# SSRPGenericTelemetryModule.net
KiCad netlist of a schematic drawn in EAGLE
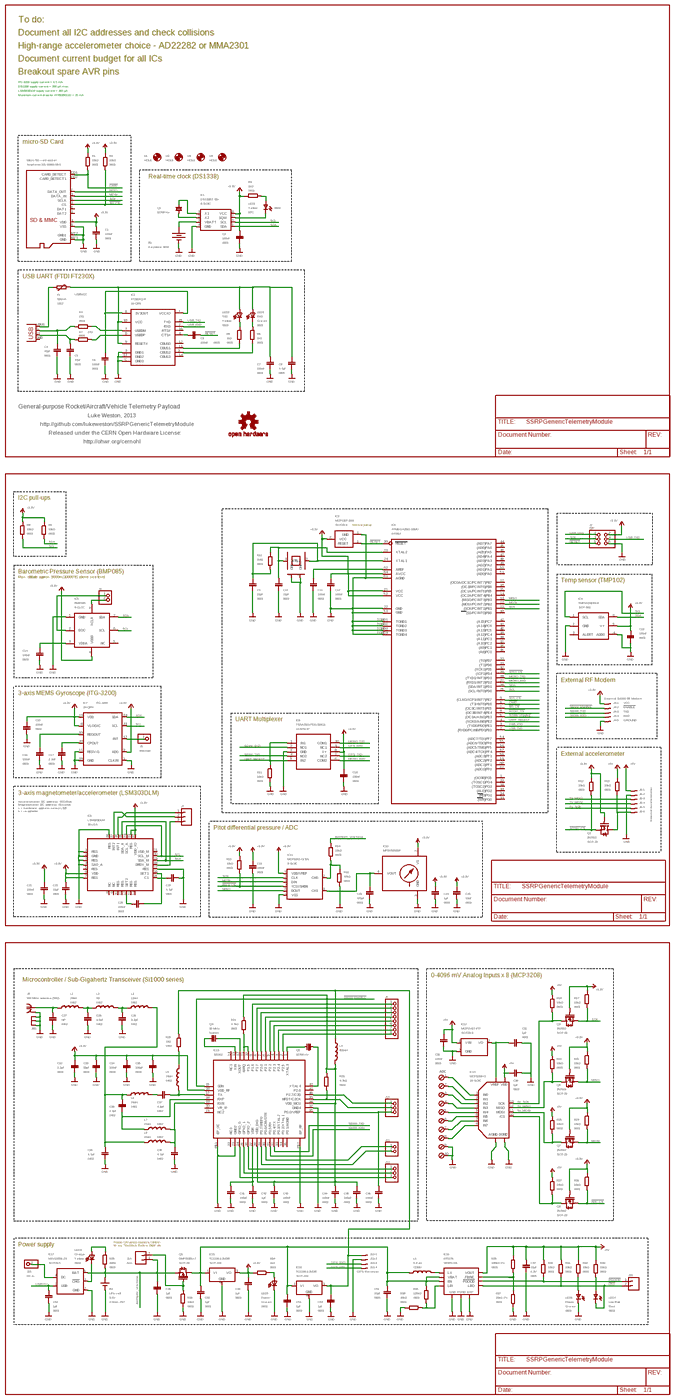
[diagram p0: schematic, sheet 1, overview]
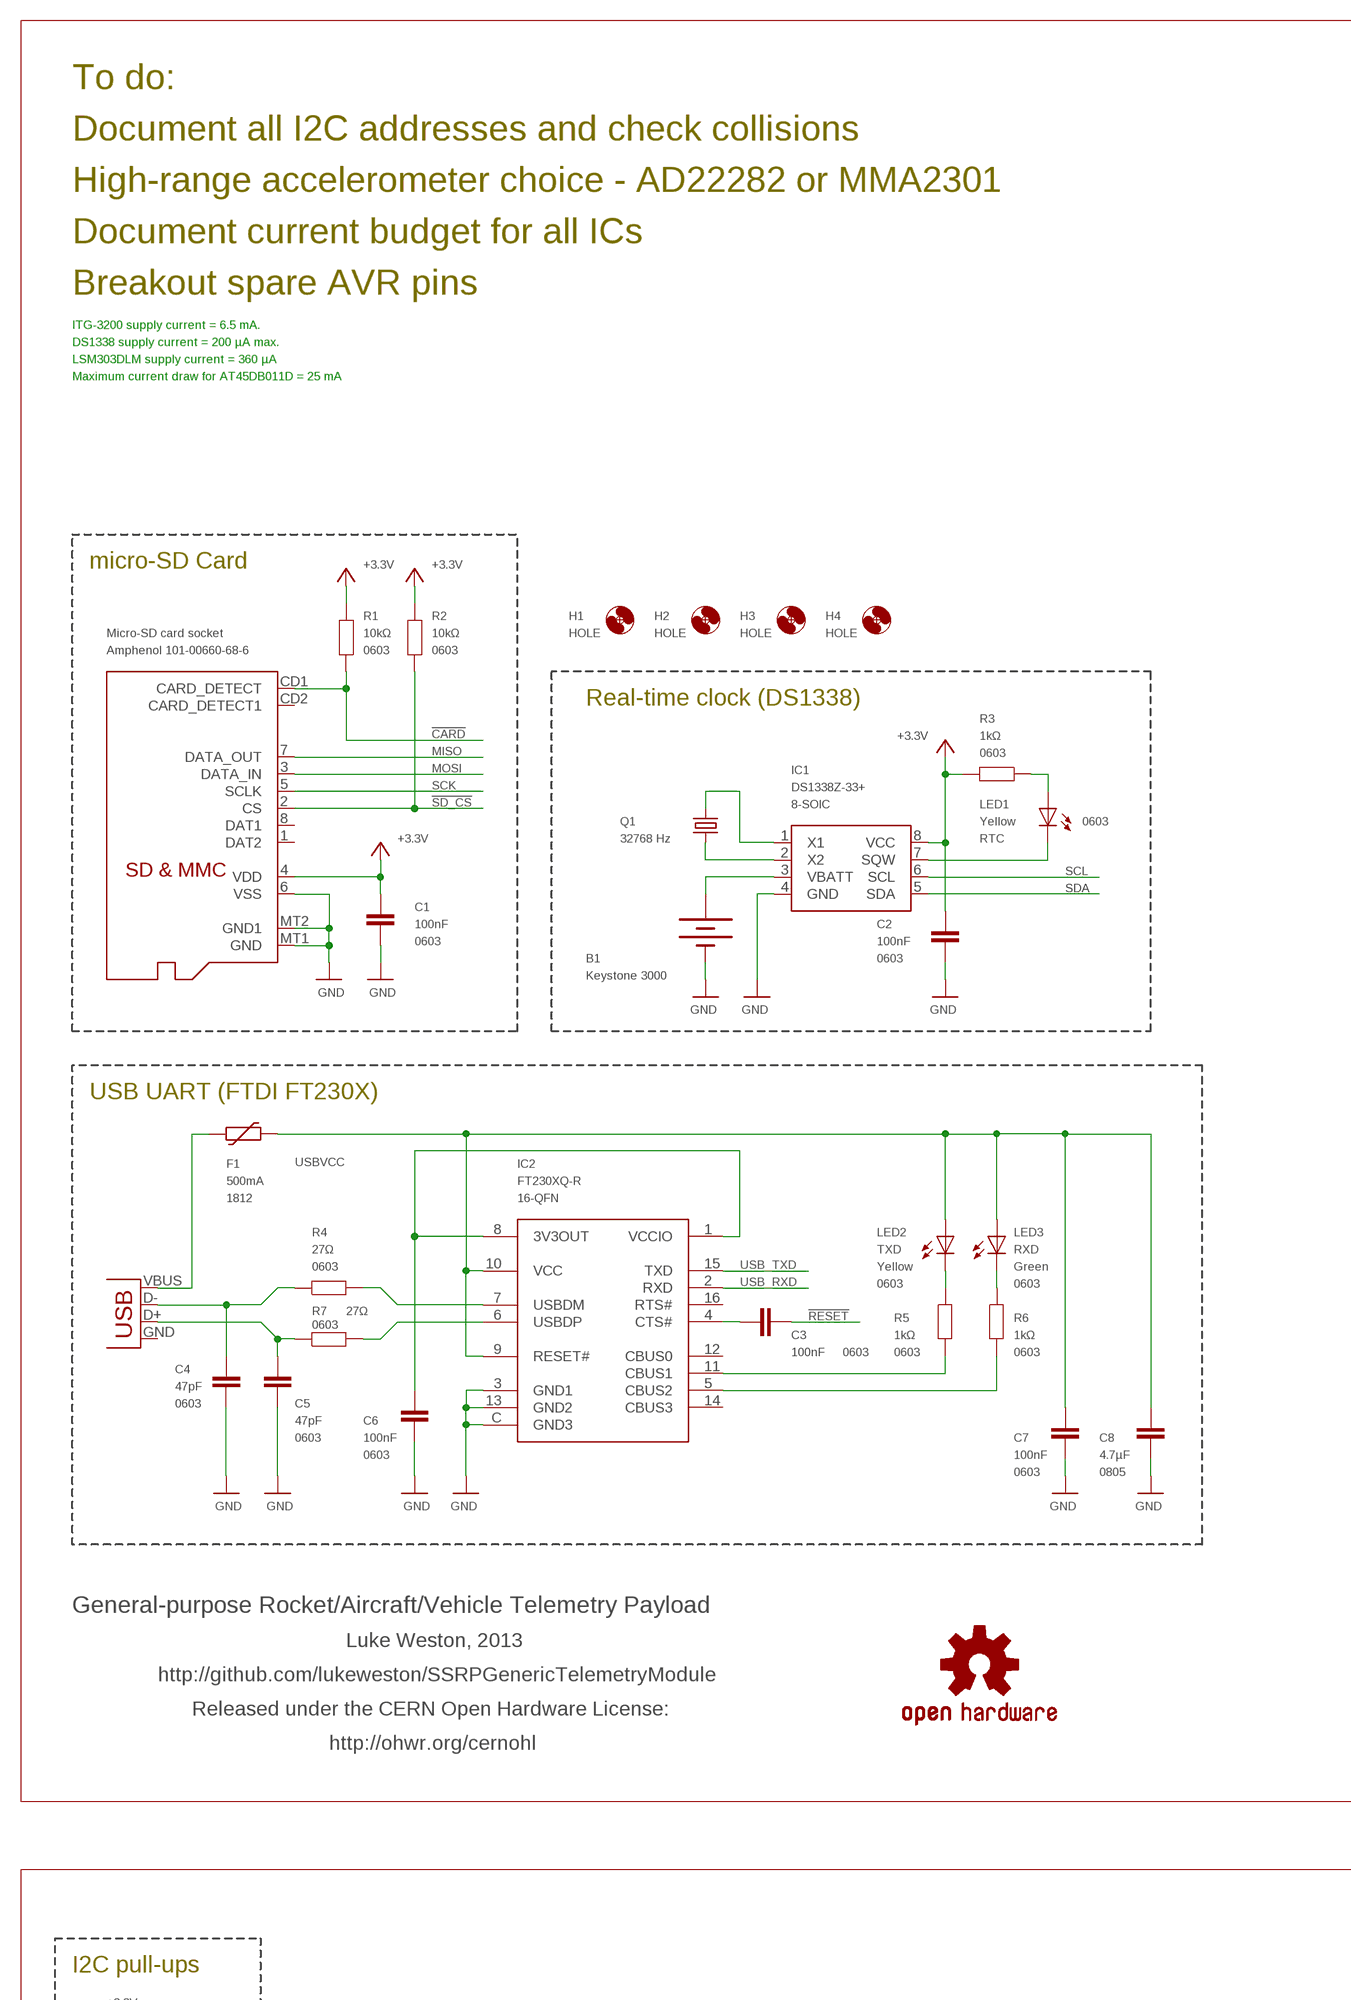
[diagram p1: schematic, sheet 1, part 1 of 6]
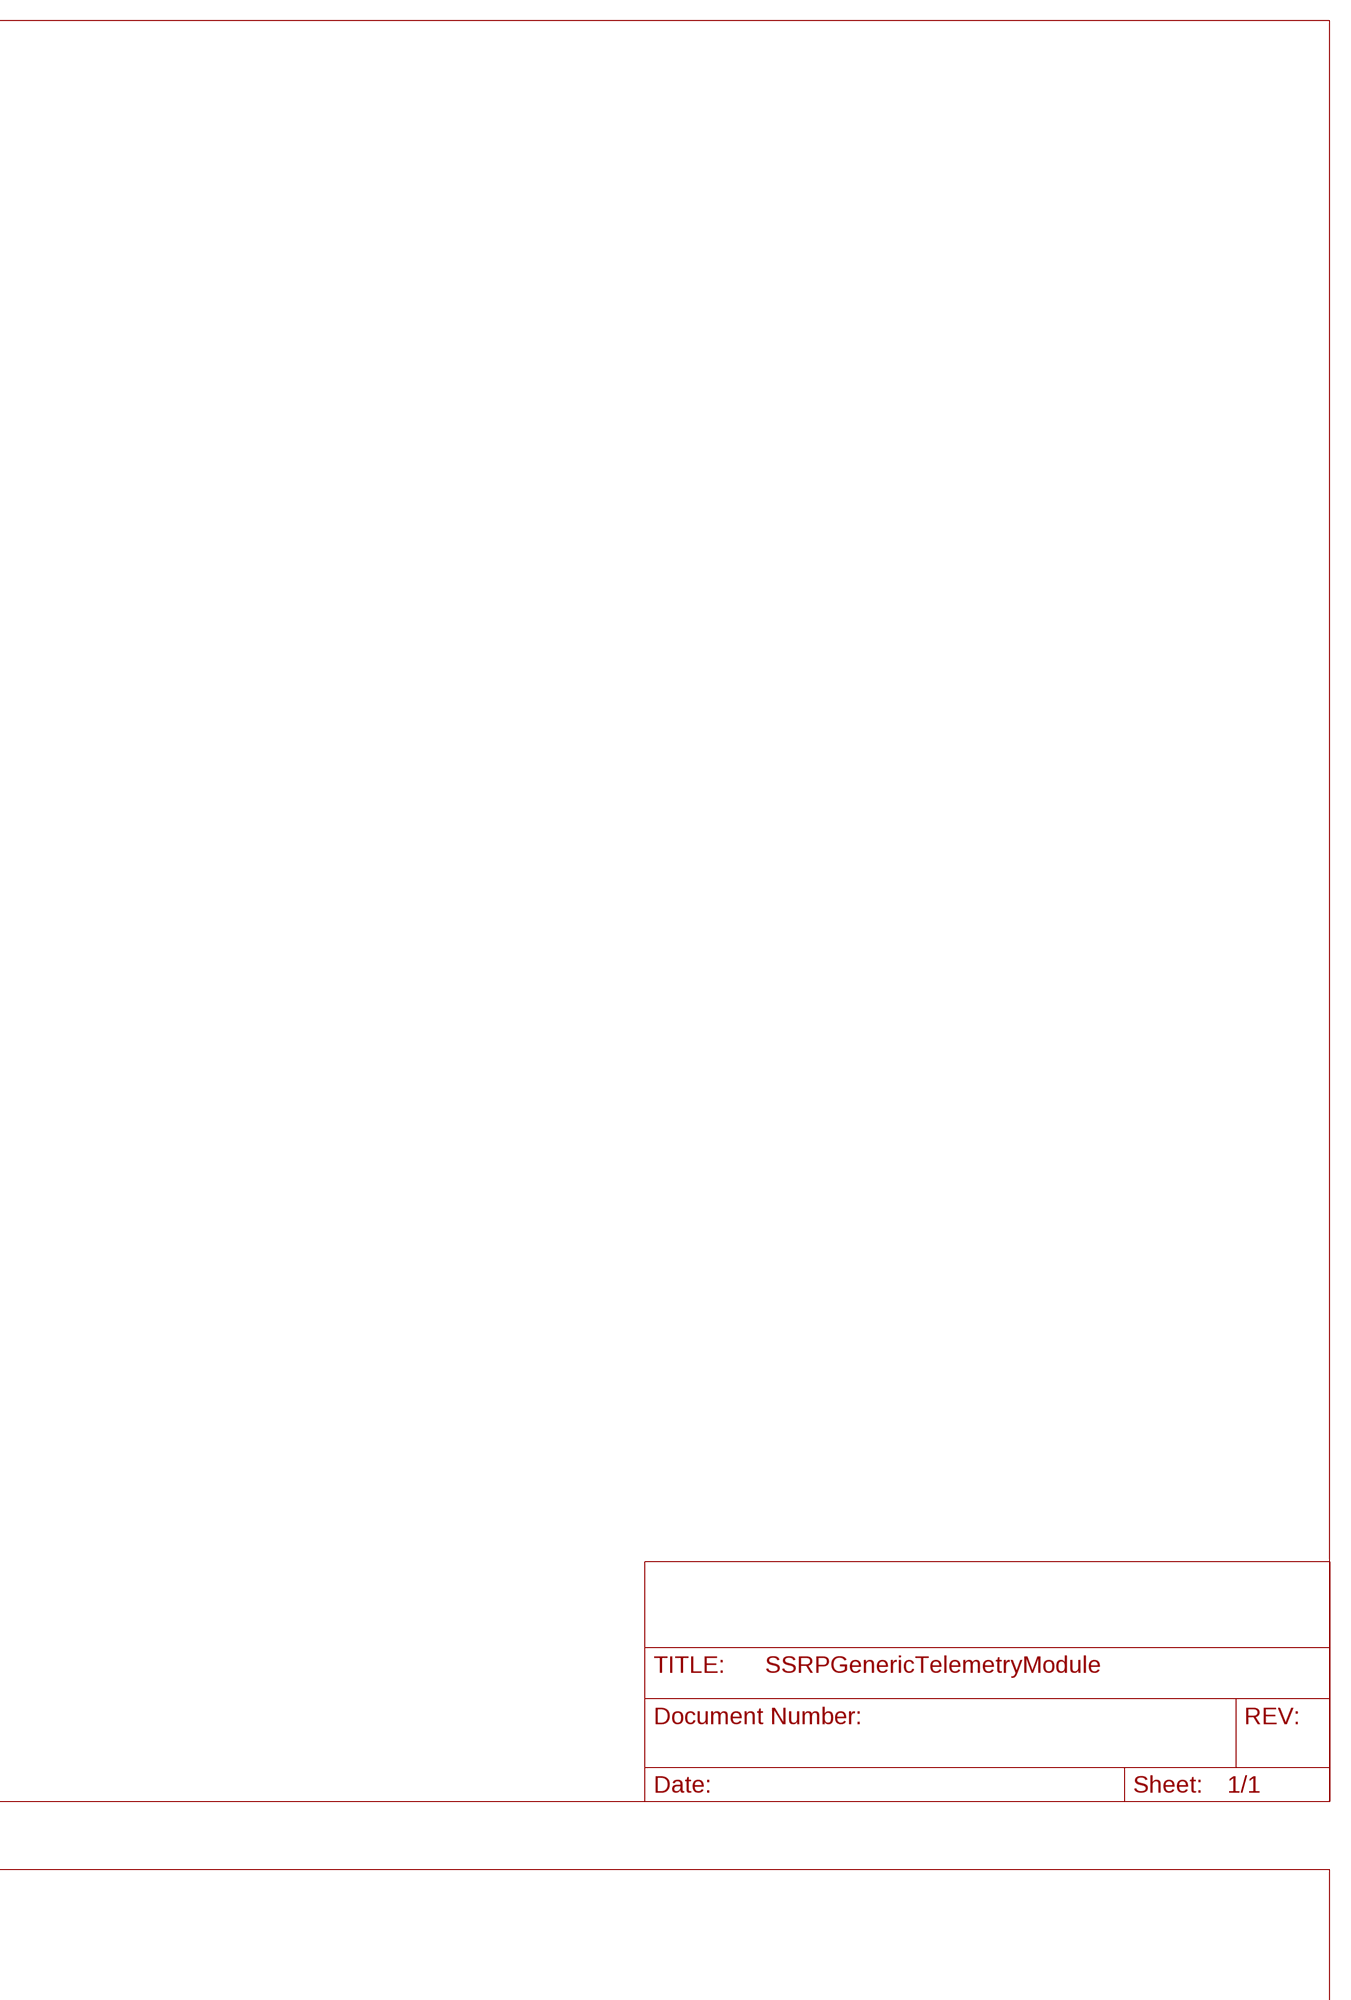
[diagram p2: schematic, sheet 1, part 2 of 6]
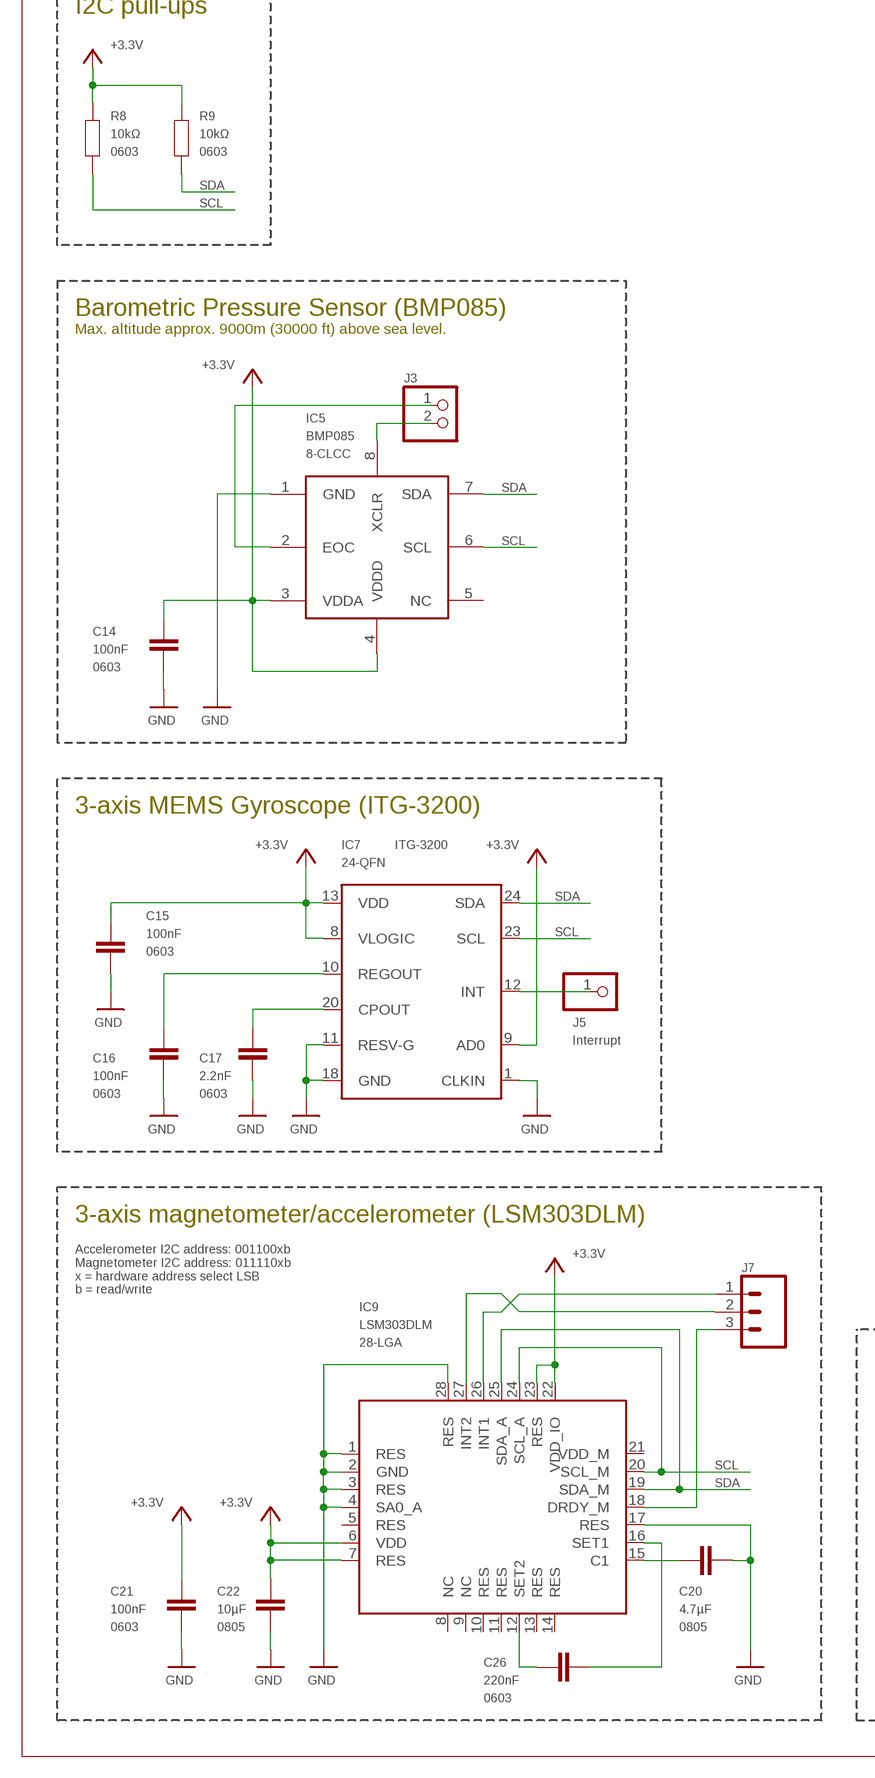
[diagram p3: schematic, sheet 1, part 3 of 6]
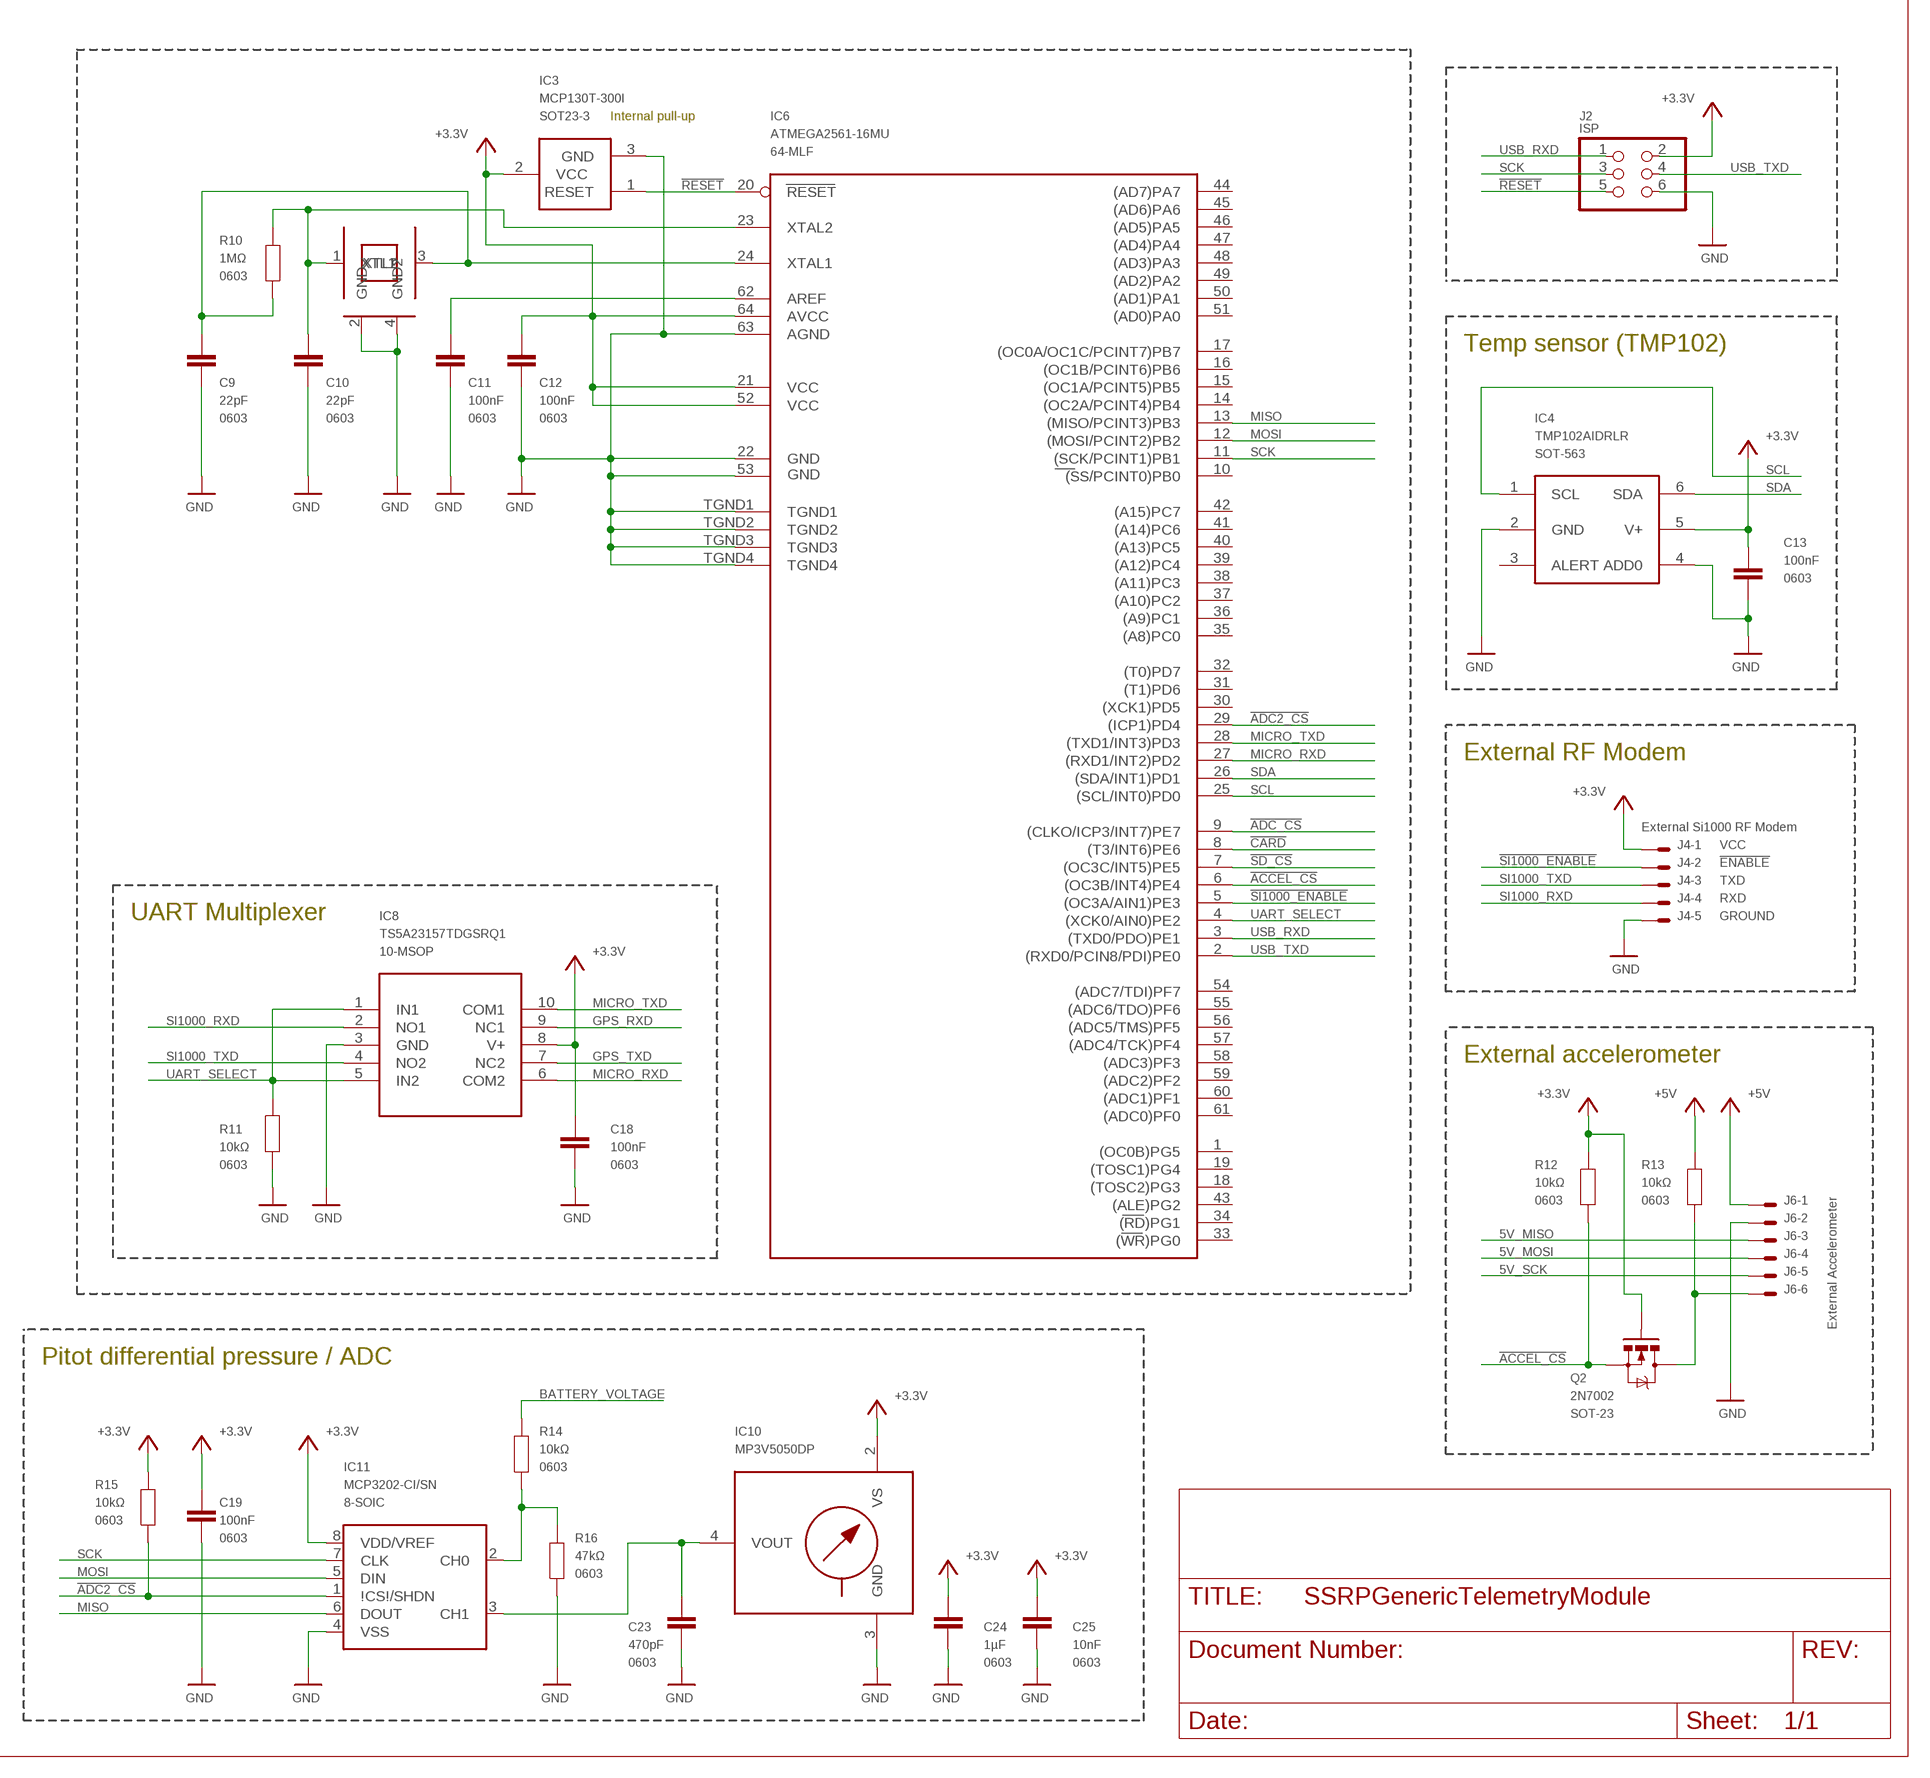
[diagram p4: schematic, sheet 1, part 4 of 6]
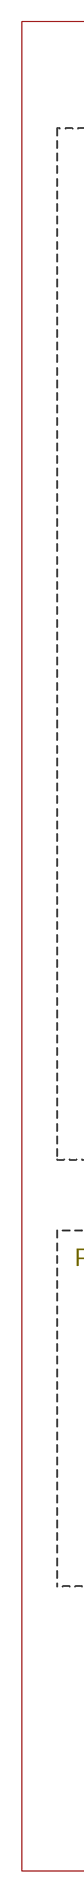
[diagram p5: schematic, sheet 1, part 5 of 6]
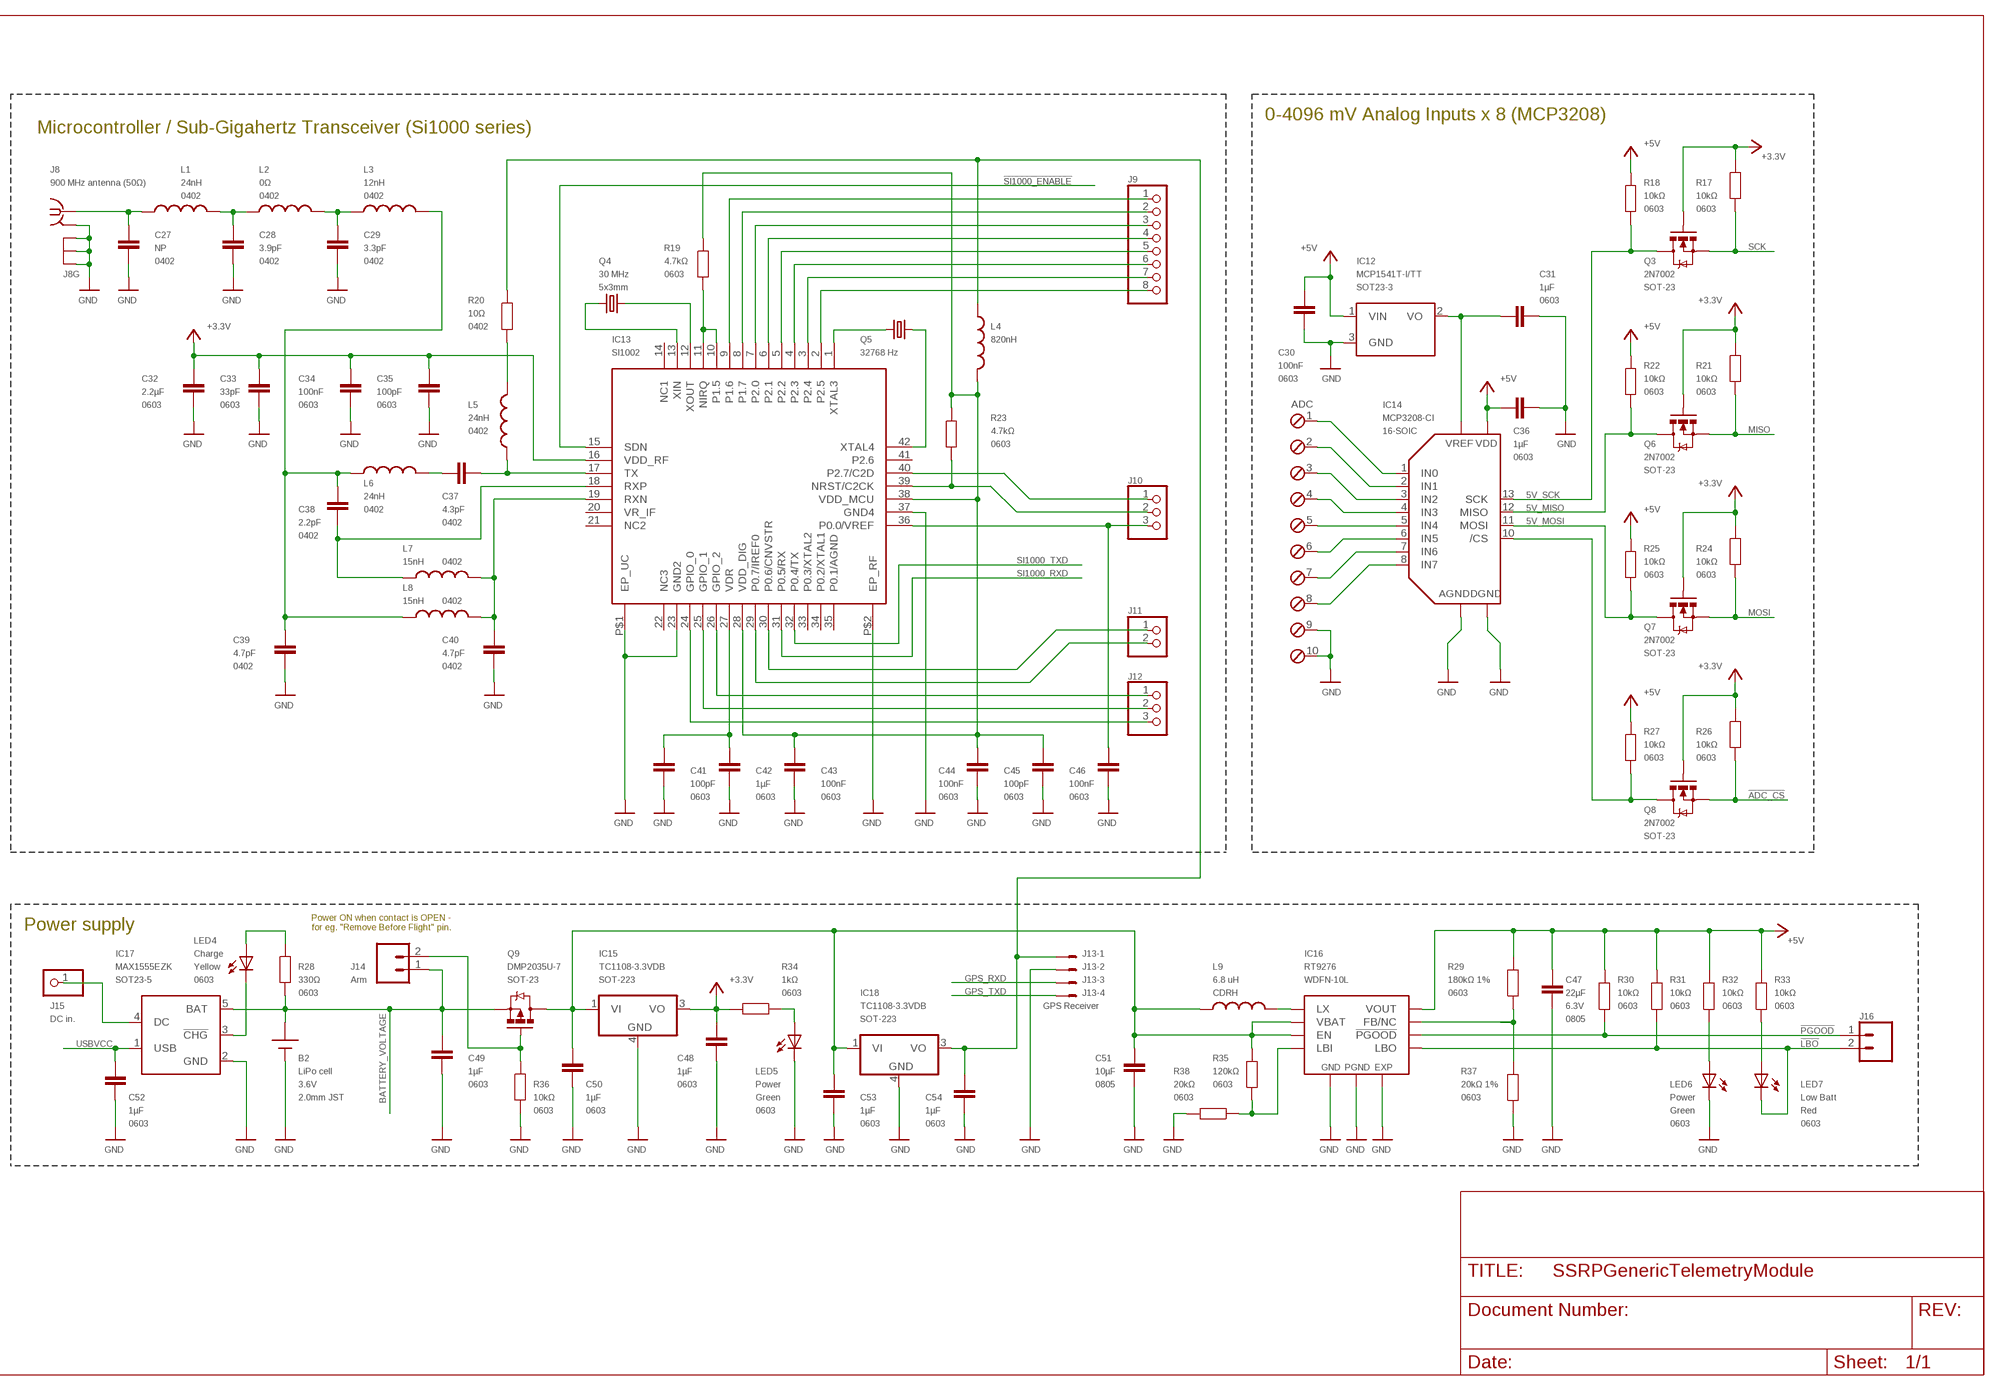
[diagram p6: schematic, sheet 1, part 6 of 6]

(export (version "E")
  (design (tool "Eeschema 10.0.6"))
  (components
    (comp (ref "B1")
      (value "Keystone 3000")
      (footprint "eagle-import:BATTCON_12MM")
      (libsource (lib "eagle-import") (part "BATTERY12MM"))
    )
    (comp (ref "B2")
      (value "LiPo cell")
      (footprint "eagle-import:JST-2MM-TH-RA")
      (fields (field (name "CONN") "2.0mm JST") (field (name "VOLTAGE") "3.6V"))
      (libsource (lib "eagle-import") (part "2P-JST-TH-RA"))
    )
    (comp (ref "C1")
      (value "100nF")
      (footprint "eagle-import:0603")
      (fields (field (name "PACKAGE") "0603"))
      (libsource (lib "eagle-import") (part "CAP0603"))
    )
    (comp (ref "C2")
      (value "100nF")
      (footprint "eagle-import:0603")
      (fields (field (name "PACKAGE") "0603"))
      (libsource (lib "eagle-import") (part "CAP0603"))
    )
    (comp (ref "C3")
      (value "100nF")
      (footprint "eagle-import:0603")
      (fields (field (name "PACKAGE") "0603"))
      (libsource (lib "eagle-import") (part "CAP0603"))
    )
    (comp (ref "C4")
      (value "47pF")
      (footprint "eagle-import:0603")
      (fields (field (name "PACKAGE") "0603"))
      (libsource (lib "eagle-import") (part "CAP0603"))
    )
    (comp (ref "C5")
      (value "47pF")
      (footprint "eagle-import:0603")
      (fields (field (name "PACKAGE") "0603"))
      (libsource (lib "eagle-import") (part "CAP0603"))
    )
    (comp (ref "C6")
      (value "100nF")
      (footprint "eagle-import:0603")
      (fields (field (name "PACKAGE") "0603"))
      (libsource (lib "eagle-import") (part "CAP0603"))
    )
    (comp (ref "C7")
      (value "100nF")
      (footprint "eagle-import:0603")
      (fields (field (name "PACKAGE") "0603"))
      (libsource (lib "eagle-import") (part "CAP0603"))
    )
    (comp (ref "C8")
      (value "4.7µF")
      (footprint "eagle-import:0805")
      (fields (field (name "PACKAGE") "0805"))
      (libsource (lib "eagle-import") (part "CAP0805"))
    )
    (comp (ref "C9")
      (value "22pF")
      (footprint "eagle-import:0603")
      (fields (field (name "PACKAGE") "0603"))
      (libsource (lib "eagle-import") (part "CAP0603"))
    )
    (comp (ref "C10")
      (value "22pF")
      (footprint "eagle-import:0603")
      (fields (field (name "PACKAGE") "0603"))
      (libsource (lib "eagle-import") (part "CAP0603"))
    )
    (comp (ref "C11")
      (value "100nF")
      (footprint "eagle-import:0603")
      (fields (field (name "PACKAGE") "0603"))
      (libsource (lib "eagle-import") (part "CAP0603"))
    )
    (comp (ref "C12")
      (value "100nF")
      (footprint "eagle-import:0603")
      (fields (field (name "PACKAGE") "0603"))
      (libsource (lib "eagle-import") (part "CAP0603"))
    )
    (comp (ref "C13")
      (value "100nF")
      (footprint "eagle-import:0603")
      (fields (field (name "PACKAGE") "0603"))
      (libsource (lib "eagle-import") (part "CAP0603"))
    )
    (comp (ref "C14")
      (value "100nF")
      (footprint "eagle-import:0603")
      (fields (field (name "PACKAGE") "0603"))
      (libsource (lib "eagle-import") (part "CAP0603"))
    )
    (comp (ref "C15")
      (value "100nF")
      (footprint "eagle-import:0603")
      (fields (field (name "PACKAGE") "0603"))
      (libsource (lib "eagle-import") (part "CAP0603"))
    )
    (comp (ref "C16")
      (value "100nF")
      (footprint "eagle-import:0603")
      (fields (field (name "PACKAGE") "0603"))
      (libsource (lib "eagle-import") (part "CAP0603"))
    )
    (comp (ref "C17")
      (value "2.2nF")
      (footprint "eagle-import:0603")
      (fields (field (name "PACKAGE") "0603"))
      (libsource (lib "eagle-import") (part "CAP0603"))
    )
    (comp (ref "C18")
      (value "100nF")
      (footprint "eagle-import:0603")
      (fields (field (name "PACKAGE") "0603"))
      (libsource (lib "eagle-import") (part "CAP0603"))
    )
    (comp (ref "C19")
      (value "100nF")
      (footprint "eagle-import:0603")
      (fields (field (name "PACKAGE") "0603"))
      (libsource (lib "eagle-import") (part "CAP0603"))
    )
    (comp (ref "C20")
      (value "4.7µF")
      (footprint "eagle-import:0805")
      (fields (field (name "PACKAGE") "0805"))
      (libsource (lib "eagle-import") (part "CAP0805"))
    )
    (comp (ref "C21")
      (value "100nF")
      (footprint "eagle-import:0603")
      (fields (field (name "PACKAGE") "0603"))
      (libsource (lib "eagle-import") (part "CAP0603"))
    )
    (comp (ref "C22")
      (value "10µF")
      (footprint "eagle-import:0805")
      (fields (field (name "PACKAGE") "0805"))
      (libsource (lib "eagle-import") (part "CAP0805"))
    )
    (comp (ref "C23")
      (value "470pF")
      (footprint "eagle-import:0603")
      (fields (field (name "PACKAGE") "0603"))
      (libsource (lib "eagle-import") (part "CAP0603"))
    )
    (comp (ref "C24")
      (value "1µF")
      (footprint "eagle-import:0603")
      (fields (field (name "PACKAGE") "0603"))
      (libsource (lib "eagle-import") (part "CAP0603"))
    )
    (comp (ref "C25")
      (value "10nF")
      (footprint "eagle-import:0603")
      (fields (field (name "PACKAGE") "0603"))
      (libsource (lib "eagle-import") (part "CAP0603"))
    )
    (comp (ref "C26")
      (value "220nF")
      (footprint "eagle-import:0603")
      (fields (field (name "PACKAGE") "0603"))
      (libsource (lib "eagle-import") (part "CAP0603"))
    )
    (comp (ref "C27")
      (value "NP")
      (footprint "eagle-import:C0402")
      (fields (field (name "PACKAGE") "0402"))
      (libsource (lib "eagle-import") (part "CAP0402"))
    )
    (comp (ref "C28")
      (value "3.9pF")
      (footprint "eagle-import:C0402")
      (fields (field (name "PACKAGE") "0402"))
      (libsource (lib "eagle-import") (part "CAP0402"))
    )
    (comp (ref "C29")
      (value "3.3pF")
      (footprint "eagle-import:C0402")
      (fields (field (name "PACKAGE") "0402"))
      (libsource (lib "eagle-import") (part "CAP0402"))
    )
    (comp (ref "C30")
      (value "100nF")
      (footprint "eagle-import:0603")
      (fields (field (name "PACKAGE") "0603"))
      (libsource (lib "eagle-import") (part "CAP0603"))
    )
    (comp (ref "C31")
      (value "1µF")
      (footprint "eagle-import:0603")
      (fields (field (name "PACKAGE") "0603"))
      (libsource (lib "eagle-import") (part "CAP0603"))
    )
    (comp (ref "C32")
      (value "2.2µF")
      (footprint "eagle-import:0603")
      (fields (field (name "PACKAGE") "0603"))
      (libsource (lib "eagle-import") (part "CAP0603"))
    )
    (comp (ref "C33")
      (value "33pF")
      (footprint "eagle-import:0603")
      (fields (field (name "PACKAGE") "0603"))
      (libsource (lib "eagle-import") (part "CAP0603"))
    )
    (comp (ref "C34")
      (value "100nF")
      (footprint "eagle-import:0603")
      (fields (field (name "PACKAGE") "0603"))
      (libsource (lib "eagle-import") (part "CAP0603"))
    )
    (comp (ref "C35")
      (value "100pF")
      (footprint "eagle-import:0603")
      (fields (field (name "PACKAGE") "0603"))
      (libsource (lib "eagle-import") (part "CAP0603"))
    )
    (comp (ref "C36")
      (value "1µF")
      (footprint "eagle-import:0603")
      (fields (field (name "PACKAGE") "0603"))
      (libsource (lib "eagle-import") (part "CAP0603"))
    )
    (comp (ref "C37")
      (value "4.3pF")
      (footprint "eagle-import:C0402")
      (fields (field (name "PACKAGE") "0402"))
      (libsource (lib "eagle-import") (part "CAP0402"))
    )
    (comp (ref "C38")
      (value "2.2pF")
      (footprint "eagle-import:C0402")
      (fields (field (name "PACKAGE") "0402"))
      (libsource (lib "eagle-import") (part "CAP0402"))
    )
    (comp (ref "C39")
      (value "4.7pF")
      (footprint "eagle-import:C0402")
      (fields (field (name "PACKAGE") "0402"))
      (libsource (lib "eagle-import") (part "CAP0402"))
    )
    (comp (ref "C40")
      (value "4.7pF")
      (footprint "eagle-import:C0402")
      (fields (field (name "PACKAGE") "0402"))
      (libsource (lib "eagle-import") (part "CAP0402"))
    )
    (comp (ref "C41")
      (value "100pF")
      (footprint "eagle-import:0603")
      (fields (field (name "PACKAGE") "0603"))
      (libsource (lib "eagle-import") (part "CAP0603"))
    )
    (comp (ref "C42")
      (value "1µF")
      (footprint "eagle-import:0603")
      (fields (field (name "PACKAGE") "0603"))
      (libsource (lib "eagle-import") (part "CAP0603"))
    )
    (comp (ref "C43")
      (value "100nF")
      (footprint "eagle-import:0603")
      (fields (field (name "PACKAGE") "0603"))
      (libsource (lib "eagle-import") (part "CAP0603"))
    )
    (comp (ref "C44")
      (value "100nF")
      (footprint "eagle-import:0603")
      (fields (field (name "PACKAGE") "0603"))
      (libsource (lib "eagle-import") (part "CAP0603"))
    )
    (comp (ref "C45")
      (value "100pF")
      (footprint "eagle-import:0603")
      (fields (field (name "PACKAGE") "0603"))
      (libsource (lib "eagle-import") (part "CAP0603"))
    )
    (comp (ref "C46")
      (value "100nF")
      (footprint "eagle-import:0603")
      (fields (field (name "PACKAGE") "0603"))
      (libsource (lib "eagle-import") (part "CAP0603"))
    )
    (comp (ref "C47")
      (value "22µF")
      (footprint "eagle-import:0805")
      (fields (field (name "PACKAGE") "0805") (field (name "VOLTAGE") "6.3V"))
      (libsource (lib "eagle-import") (part "CAP0805"))
    )
    (comp (ref "C48")
      (value "1µF")
      (footprint "eagle-import:0603")
      (fields (field (name "PACKAGE") "0603"))
      (libsource (lib "eagle-import") (part "CAP0603"))
    )
    (comp (ref "C49")
      (value "1µF")
      (footprint "eagle-import:0603")
      (fields (field (name "PACKAGE") "0603"))
      (libsource (lib "eagle-import") (part "CAP0603"))
    )
    (comp (ref "C50")
      (value "1µF")
      (footprint "eagle-import:0603")
      (fields (field (name "PACKAGE") "0603"))
      (libsource (lib "eagle-import") (part "CAP0603"))
    )
    (comp (ref "C51")
      (value "10µF")
      (footprint "eagle-import:0805")
      (fields (field (name "PACKAGE") "0805"))
      (libsource (lib "eagle-import") (part "CAP0805"))
    )
    (comp (ref "C52")
      (value "1µF")
      (footprint "eagle-import:0603")
      (fields (field (name "PACKAGE") "0603"))
      (libsource (lib "eagle-import") (part "CAP0603"))
    )
    (comp (ref "C53")
      (value "1µF")
      (footprint "eagle-import:0603")
      (fields (field (name "PACKAGE") "0603"))
      (libsource (lib "eagle-import") (part "CAP0603"))
    )
    (comp (ref "C54")
      (value "1µF")
      (footprint "eagle-import:0603")
      (fields (field (name "PACKAGE") "0603"))
      (libsource (lib "eagle-import") (part "CAP0603"))
    )
    (comp (ref "F1")
      (value "500mA")
      (footprint "eagle-import:1812")
      (fields (field (name "PACKAGE") "1812"))
      (libsource (lib "eagle-import") (part "PTC"))
    )
    (comp (ref "H1")
      (value "HOLE")
      (footprint "eagle-import:3,2")
      (libsource (lib "eagle-import") (part "MOUNT-HOLE3.2"))
    )
    (comp (ref "H2")
      (value "HOLE")
      (footprint "eagle-import:3,2")
      (libsource (lib "eagle-import") (part "MOUNT-HOLE3.2"))
    )
    (comp (ref "H3")
      (value "HOLE")
      (footprint "eagle-import:3,2")
      (libsource (lib "eagle-import") (part "MOUNT-HOLE3.2"))
    )
    (comp (ref "H4")
      (value "HOLE")
      (footprint "eagle-import:3,2")
      (libsource (lib "eagle-import") (part "MOUNT-HOLE3.2"))
    )
    (comp (ref "IC1")
      (value "DS1338Z-33+")
      (footprint "eagle-import:SO08@1")
      (fields (field (name "PACKAGE") "8-SOIC"))
      (libsource (lib "eagle-import") (part "DS1307SO8"))
    )
    (comp (ref "IC2")
      (value "FT230XQ-R")
      (footprint "eagle-import:QFN4X4-16")
      (fields (field (name "PACKAGE") "16-QFN"))
      (libsource (lib "eagle-import") (part "FT230XQ"))
    )
    (comp (ref "IC3")
      (value "MCP130T-300I")
      (footprint "eagle-import:SOT23-3")
      (fields (field (name "PACKAGE") "SOT23-3"))
      (libsource (lib "eagle-import") (part "MCP130SOT"))
    )
    (comp (ref "IC4")
      (value "TMP102AIDRLR")
      (footprint "eagle-import:SOT563")
      (fields (field (name "PACKAGE") "SOT-563"))
      (libsource (lib "eagle-import") (part "TMP102"))
    )
    (comp (ref "IC5")
      (value "BMP085")
      (footprint "eagle-import:BMP085")
      (libsource (lib "eagle-import") (part "BMP085"))
    )
    (comp (ref "IC6")
      (value "ATMEGA2561-16MU")
      (footprint "eagle-import:MLF64")
      (fields (field (name "PACKAGE") "64-MLF"))
      (libsource (lib "eagle-import") (part "ATMEGA2561MU-16"))
    )
    (comp (ref "IC7")
      (value "ITG-3200")
      (footprint "eagle-import:QFN-24")
      (fields (field (name "PACKAGE") "24-QFN"))
      (libsource (lib "eagle-import") (part "ITG-3200"))
    )
    (comp (ref "IC8")
      (value "TS5A23157TDGSRQ1")
      (footprint "eagle-import:MSOP10")
      (fields (field (name "PACKAGE") "10-MSOP"))
      (libsource (lib "eagle-import") (part "TS5A23157"))
    )
    (comp (ref "IC9")
      (value "LSM303DLM")
      (footprint "eagle-import:LGA28-5X5")
      (fields (field (name "PACKAGE") "28-LGA"))
      (libsource (lib "eagle-import") (part "LSM303DLHSMD"))
    )
    (comp (ref "IC10")
      (value "MP3V5050DP")
      (footprint "eagle-import:1351")
      (libsource (lib "eagle-import") (part "MPXV5004GDP"))
    )
    (comp (ref "IC11")
      (value "MCP3202-CI/SN")
      (footprint "eagle-import:SO-08")
      (fields (field (name "PACKAGE") "8-SOIC"))
      (libsource (lib "eagle-import") (part "MCP3202SN"))
    )
    (comp (ref "IC12")
      (value "MCP1541T-I/TT")
      (footprint "eagle-import:SOT23")
      (fields (field (name "PACKAGE") "SOT23-3"))
      (libsource (lib "eagle-import") (part "MC15TT41"))
    )
    (comp (ref "IC13")
      (value "SI1002")
      (footprint "eagle-import:QFN42_MCM")
      (libsource (lib "eagle-import") (part "SI1001NORMAL"))
    )
    (comp (ref "IC14")
      (value "MCP3208-CI")
      (footprint "eagle-import:SOIC16")
      (fields (field (name "PACKAGE") "16-SOIC"))
      (libsource (lib "eagle-import") (part "MCP3208MCP3208-SOIC"))
    )
    (comp (ref "IC15")
      (value "TC1108-3.3VDB")
      (footprint "eagle-import:SOT223")
      (fields (field (name "PACKAGE") "SOT-223"))
      (libsource (lib "eagle-import") (part "LM340?-MP05"))
    )
    (comp (ref "IC16")
      (value "RT9276")
      (footprint "eagle-import:WDFN-10L-3X3")
      (fields (field (name "PACKAGE") "WDFN-10L"))
      (libsource (lib "eagle-import") (part "RT9276"))
    )
    (comp (ref "IC17")
      (value "MAX1555EZK")
      (footprint "eagle-import:SOT23-5L")
      (fields
        (field (name "MF") "MAXIM")
        (field (name "MPN") "MAX1555EZK+T")
        (field (name "PACKAGE") "SOT23-5")
      )
      (libsource (lib "eagle-import") (part "MAX1555"))
    )
    (comp (ref "IC18")
      (value "TC1108-3.3VDB")
      (footprint "eagle-import:SOT223")
      (fields (field (name "PACKAGE") "SOT-223"))
      (libsource (lib "eagle-import") (part "LM340?-MP05"))
    )
    (comp (ref "J1")
      (value "MicroSD Card")
      (footprint "eagle-import:ADAFRUIT_MICROSD")
      (libsource (lib "eagle-import") (part "ADAFRUIT_MICROSD"))
    )
    (comp (ref "J2")
      (value "ISP")
      (footprint "eagle-import:2X03PTH")
      (libsource (lib "eagle-import") (part "ICSPPTH"))
    )
    (comp (ref "J3")
      (value "PINHD-1X2")
      (footprint "eagle-import:1X02")
      (libsource (lib "eagle-import") (part "PINHD-1X2"))
    )
    (comp (ref "J4")
      (value "External Si1000 RF Modem")
      (footprint "eagle-import:22-23-2051")
      (fields (field (name "MF") "MOLEX") (field (name "MPN") "22-23-2051"))
      (libsource (lib "eagle-import") (part "22-23-2051"))
    )
    (comp (ref "J5")
      (value "Interrupt")
      (footprint "eagle-import:1X01")
      (libsource (lib "eagle-import") (part "PINHD-1X1"))
    )
    (comp (ref "J6")
      (value "External Accelerometer")
      (footprint "eagle-import:7395-06")
      (libsource (lib "eagle-import") (part "22-?-0605-7068"))
    )
    (comp (ref "J7")
      (value "M03PTH")
      (footprint "eagle-import:1X03")
      (libsource (lib "eagle-import") (part "M03PTH"))
    )
    (comp (ref "J8")
      (value "900 MHz antenna (50Ω)")
      (footprint "eagle-import:J502-ND-142-0701-801_806")
      (fields (field (name "MF") "JOHNSON COMPONENTS") (field (name "MPN") "142-0701-801"))
      (libsource (lib "eagle-import") (part "SMA-142-0701-801/806"))
    )
    (comp (ref "J9")
      (value "PINHD-1X8")
      (footprint "eagle-import:1X08")
      (libsource (lib "eagle-import") (part "PINHD-1X8"))
    )
    (comp (ref "J10")
      (value "PINHD-1X3")
      (footprint "eagle-import:1X03")
      (libsource (lib "eagle-import") (part "PINHD-1X3"))
    )
    (comp (ref "J11")
      (value "PINHD-1X2")
      (footprint "eagle-import:1X02")
      (libsource (lib "eagle-import") (part "PINHD-1X2"))
    )
    (comp (ref "J12")
      (value "PINHD-1X3")
      (footprint "eagle-import:1X03")
      (libsource (lib "eagle-import") (part "PINHD-1X3"))
    )
    (comp (ref "J13")
      (value "GPS Receiver")
      (footprint "eagle-import:7395-04")
      (libsource (lib "eagle-import") (part "22-?-0405-7048"))
    )
    (comp (ref "J14")
      (value "Arm")
      (footprint "eagle-import:1X02")
      (libsource (lib "eagle-import") (part "M02PTH"))
    )
    (comp (ref "J15")
      (value "DC in.")
      (footprint "eagle-import:1X01")
      (libsource (lib "eagle-import") (part "PINHD-1X1"))
    )
    (comp (ref "J16")
      (value "Status")
      (footprint "eagle-import:1X02")
      (libsource (lib "eagle-import") (part "M02PTH"))
    )
    (comp (ref "L1")
      (value "24nH")
      (footprint "eagle-import:C0402")
      (fields (field (name "PACKAGE") "0402"))
      (libsource (lib "eagle-import") (part "INDUCTOR0402"))
    )
    (comp (ref "L2")
      (value "0Ω")
      (footprint "eagle-import:C0402")
      (fields (field (name "PACKAGE") "0402"))
      (libsource (lib "eagle-import") (part "INDUCTOR0402"))
    )
    (comp (ref "L3")
      (value "12nH")
      (footprint "eagle-import:C0402")
      (fields (field (name "PACKAGE") "0402"))
      (libsource (lib "eagle-import") (part "INDUCTOR0402"))
    )
    (comp (ref "L4")
      (value "820nH")
      (footprint "eagle-import:C0402")
      (libsource (lib "eagle-import") (part "INDUCTOR0402"))
    )
    (comp (ref "L5")
      (value "24nH")
      (footprint "eagle-import:C0402")
      (fields (field (name "PACKAGE") "0402"))
      (libsource (lib "eagle-import") (part "INDUCTOR0402"))
    )
    (comp (ref "L6")
      (value "24nH")
      (footprint "eagle-import:C0402")
      (fields (field (name "PACKAGE") "0402"))
      (libsource (lib "eagle-import") (part "INDUCTOR0402"))
    )
    (comp (ref "L7")
      (value "15nH")
      (footprint "eagle-import:C0402")
      (fields (field (name "PACKAGE") "0402"))
      (libsource (lib "eagle-import") (part "INDUCTOR0402"))
    )
    (comp (ref "L8")
      (value "15nH")
      (footprint "eagle-import:C0402")
      (fields (field (name "PACKAGE") "0402"))
      (libsource (lib "eagle-import") (part "INDUCTOR0402"))
    )
    (comp (ref "L9")
      (value "6.8 uH")
      (footprint "eagle-import:CDRH")
      (fields (field (name "PACKAGE") "CDRH"))
      (libsource (lib "eagle-import") (part "INDUCTOR"))
    )
    (comp (ref "LED1")
      (value "RTC")
      (footprint "eagle-import:LED-0603")
      (fields (field (name "COLOUR") "Yellow") (field (name "PACKAGE") "0603"))
      (libsource (lib "eagle-import") (part "LED0603"))
    )
    (comp (ref "LED2")
      (value "TXD")
      (footprint "eagle-import:LED-0603")
      (fields (field (name "COLOUR") "Yellow") (field (name "PACKAGE") "0603"))
      (libsource (lib "eagle-import") (part "LED0603"))
    )
    (comp (ref "LED3")
      (value "RXD")
      (footprint "eagle-import:LED-0603")
      (fields (field (name "COLOUR") "Green") (field (name "PACKAGE") "0603"))
      (libsource (lib "eagle-import") (part "LED0603"))
    )
    (comp (ref "LED4")
      (value "Charge")
      (footprint "eagle-import:LED-0603")
      (fields (field (name "COLOUR") "Yellow") (field (name "PACKAGE") "0603"))
      (libsource (lib "eagle-import") (part "LED0603"))
    )
    (comp (ref "LED5")
      (value "Power")
      (footprint "eagle-import:LED-0603")
      (fields (field (name "COLOUR") "Green") (field (name "PACKAGE") "0603"))
      (libsource (lib "eagle-import") (part "LED0603"))
    )
    (comp (ref "LED6")
      (value "Power")
      (footprint "eagle-import:LED-0603")
      (fields (field (name "COLOUR") "Green") (field (name "PACKAGE") "0603"))
      (libsource (lib "eagle-import") (part "LED0603"))
    )
    (comp (ref "LED7")
      (value "Low Batt")
      (footprint "eagle-import:LED-0603")
      (fields (field (name "COLOUR") "Red") (field (name "PACKAGE") "0603"))
      (libsource (lib "eagle-import") (part "LED0603"))
    )
    (comp (ref "Q1")
      (value "32768 Hz")
      (footprint "eagle-import:SMD3215_XTAL")
      (libsource (lib "eagle-import") (part "CRYSTAL-SMD3215_TST"))
    )
    (comp (ref "Q2")
      (value "2N7002")
      (footprint "eagle-import:SOT23-3")
      (fields (field (name "PACKAGE") "SOT-23"))
      (libsource (lib "eagle-import") (part "MOSFET-NCHANNELSMD"))
    )
    (comp (ref "Q3")
      (value "2N7002")
      (footprint "eagle-import:SOT23-3")
      (fields (field (name "PACKAGE") "SOT-23"))
      (libsource (lib "eagle-import") (part "MOSFET-NCHANNELSMD"))
    )
    (comp (ref "Q4")
      (value "30 MHz")
      (footprint "eagle-import:CRYSTAL-SMD-5X3")
      (fields (field (name "PACKAGE") "5x3mm"))
      (libsource (lib "eagle-import") (part "CRYSTAL5X3"))
    )
    (comp (ref "Q5")
      (value "32768 Hz")
      (footprint "eagle-import:SMD3215_XTAL")
      (libsource (lib "eagle-import") (part "CRYSTAL-SMD3215_TST"))
    )
    (comp (ref "Q6")
      (value "2N7002")
      (footprint "eagle-import:SOT23-3")
      (fields (field (name "PACKAGE") "SOT-23"))
      (libsource (lib "eagle-import") (part "MOSFET-NCHANNELSMD"))
    )
    (comp (ref "Q7")
      (value "2N7002")
      (footprint "eagle-import:SOT23-3")
      (fields (field (name "PACKAGE") "SOT-23"))
      (libsource (lib "eagle-import") (part "MOSFET-NCHANNELSMD"))
    )
    (comp (ref "Q8")
      (value "2N7002")
      (footprint "eagle-import:SOT23-3")
      (fields (field (name "PACKAGE") "SOT-23"))
      (libsource (lib "eagle-import") (part "MOSFET-NCHANNELSMD"))
    )
    (comp (ref "Q9")
      (value "DMP2035U-7")
      (footprint "eagle-import:SOT23-3")
      (fields (field (name "PACKAGE") "SOT-23"))
      (libsource (lib "eagle-import") (part "DMP2035U-7"))
    )
    (comp (ref "R1")
      (value "10kΩ")
      (footprint "eagle-import:0603")
      (fields (field (name "PACKAGE") "0603"))
      (libsource (lib "eagle-import") (part "RESISTOR0603"))
    )
    (comp (ref "R2")
      (value "10kΩ")
      (footprint "eagle-import:0603")
      (fields (field (name "PACKAGE") "0603"))
      (libsource (lib "eagle-import") (part "RESISTOR0603"))
    )
    (comp (ref "R3")
      (value "1kΩ")
      (footprint "eagle-import:0603")
      (fields (field (name "PACKAGE") "0603"))
      (libsource (lib "eagle-import") (part "RESISTOR0603"))
    )
    (comp (ref "R4")
      (value "27Ω")
      (footprint "eagle-import:0603")
      (fields (field (name "PACKAGE") "0603"))
      (libsource (lib "eagle-import") (part "RESISTOR0603"))
    )
    (comp (ref "R5")
      (value "1kΩ")
      (footprint "eagle-import:0603")
      (fields (field (name "PACKAGE") "0603"))
      (libsource (lib "eagle-import") (part "RESISTOR0603"))
    )
    (comp (ref "R6")
      (value "1kΩ")
      (footprint "eagle-import:0603")
      (fields (field (name "PACKAGE") "0603"))
      (libsource (lib "eagle-import") (part "RESISTOR0603"))
    )
    (comp (ref "R7")
      (value "27Ω")
      (footprint "eagle-import:0603")
      (fields (field (name "PACKAGE") "0603"))
      (libsource (lib "eagle-import") (part "RESISTOR0603"))
    )
    (comp (ref "R8")
      (value "10kΩ")
      (footprint "eagle-import:0603")
      (fields (field (name "PACKAGE") "0603"))
      (libsource (lib "eagle-import") (part "RESISTOR0603"))
    )
    (comp (ref "R9")
      (value "10kΩ")
      (footprint "eagle-import:0603")
      (fields (field (name "PACKAGE") "0603"))
      (libsource (lib "eagle-import") (part "RESISTOR0603"))
    )
    (comp (ref "R10")
      (value "1MΩ")
      (footprint "eagle-import:0603")
      (fields (field (name "PACKAGE") "0603"))
      (libsource (lib "eagle-import") (part "RESISTOR0603"))
    )
    (comp (ref "R11")
      (value "10kΩ")
      (footprint "eagle-import:0603")
      (fields (field (name "PACKAGE") "0603"))
      (libsource (lib "eagle-import") (part "RESISTOR0603"))
    )
    (comp (ref "R12")
      (value "10kΩ")
      (footprint "eagle-import:0603")
      (fields (field (name "PACKAGE") "0603"))
      (libsource (lib "eagle-import") (part "RESISTOR0603"))
    )
    (comp (ref "R13")
      (value "10kΩ")
      (footprint "eagle-import:0603")
      (fields (field (name "PACKAGE") "0603"))
      (libsource (lib "eagle-import") (part "RESISTOR0603"))
    )
    (comp (ref "R14")
      (value "10kΩ")
      (footprint "eagle-import:0603")
      (fields (field (name "PACKAGE") "0603"))
      (libsource (lib "eagle-import") (part "RESISTOR0603"))
    )
    (comp (ref "R15")
      (value "10kΩ")
      (footprint "eagle-import:0603")
      (fields (field (name "PACKAGE") "0603"))
      (libsource (lib "eagle-import") (part "RESISTOR0603"))
    )
    (comp (ref "R16")
      (value "47kΩ")
      (footprint "eagle-import:0603")
      (fields (field (name "PACKAGE") "0603"))
      (libsource (lib "eagle-import") (part "RESISTOR0603"))
    )
    (comp (ref "R17")
      (value "10kΩ")
      (footprint "eagle-import:0603")
      (fields (field (name "PACKAGE") "0603"))
      (libsource (lib "eagle-import") (part "RESISTOR0603"))
    )
    (comp (ref "R18")
      (value "10kΩ")
      (footprint "eagle-import:0603")
      (fields (field (name "PACKAGE") "0603"))
      (libsource (lib "eagle-import") (part "RESISTOR0603"))
    )
    (comp (ref "R19")
      (value "4.7kΩ")
      (footprint "eagle-import:0603")
      (fields (field (name "PACKAGE") "0603"))
      (libsource (lib "eagle-import") (part "RESISTOR0603"))
    )
    (comp (ref "R20")
      (value "10Ω")
      (footprint "eagle-import:C0402")
      (fields (field (name "PACKAGE") "0402"))
      (libsource (lib "eagle-import") (part "RESISTOR0402"))
    )
    (comp (ref "R21")
      (value "10kΩ")
      (footprint "eagle-import:0603")
      (fields (field (name "PACKAGE") "0603"))
      (libsource (lib "eagle-import") (part "RESISTOR0603"))
    )
    (comp (ref "R22")
      (value "10kΩ")
      (footprint "eagle-import:0603")
      (fields (field (name "PACKAGE") "0603"))
      (libsource (lib "eagle-import") (part "RESISTOR0603"))
    )
    (comp (ref "R23")
      (value "4.7kΩ")
      (footprint "eagle-import:0603")
      (fields (field (name "PACKAGE") "0603"))
      (libsource (lib "eagle-import") (part "RESISTOR0603"))
    )
    (comp (ref "R24")
      (value "10kΩ")
      (footprint "eagle-import:0603")
      (fields (field (name "PACKAGE") "0603"))
      (libsource (lib "eagle-import") (part "RESISTOR0603"))
    )
    (comp (ref "R25")
      (value "10kΩ")
      (footprint "eagle-import:0603")
      (fields (field (name "PACKAGE") "0603"))
      (libsource (lib "eagle-import") (part "RESISTOR0603"))
    )
    (comp (ref "R26")
      (value "10kΩ")
      (footprint "eagle-import:0603")
      (fields (field (name "PACKAGE") "0603"))
      (libsource (lib "eagle-import") (part "RESISTOR0603"))
    )
    (comp (ref "R27")
      (value "10kΩ")
      (footprint "eagle-import:0603")
      (fields (field (name "PACKAGE") "0603"))
      (libsource (lib "eagle-import") (part "RESISTOR0603"))
    )
    (comp (ref "R28")
      (value "330Ω")
      (footprint "eagle-import:0603")
      (fields (field (name "PACKAGE") "0603"))
      (libsource (lib "eagle-import") (part "RESISTOR0603"))
    )
    (comp (ref "R29")
      (value "180kΩ 1%")
      (footprint "eagle-import:0603")
      (fields (field (name "PACKAGE") "0603"))
      (libsource (lib "eagle-import") (part "RESISTOR0603"))
    )
    (comp (ref "R30")
      (value "10kΩ")
      (footprint "eagle-import:0603")
      (fields (field (name "PACKAGE") "0603"))
      (libsource (lib "eagle-import") (part "RESISTOR0603"))
    )
    (comp (ref "R31")
      (value "10kΩ")
      (footprint "eagle-import:0603")
      (fields (field (name "PACKAGE") "0603"))
      (libsource (lib "eagle-import") (part "RESISTOR0603"))
    )
    (comp (ref "R32")
      (value "10kΩ")
      (footprint "eagle-import:0603")
      (fields (field (name "PACKAGE") "0603"))
      (libsource (lib "eagle-import") (part "RESISTOR0603"))
    )
    (comp (ref "R33")
      (value "10kΩ")
      (footprint "eagle-import:0603")
      (fields (field (name "PACKAGE") "0603"))
      (libsource (lib "eagle-import") (part "RESISTOR0603"))
    )
    (comp (ref "R34")
      (value "1kΩ")
      (footprint "eagle-import:0603")
      (fields (field (name "PACKAGE") "0603"))
      (libsource (lib "eagle-import") (part "RESISTOR0603"))
    )
    (comp (ref "R35")
      (value "120kΩ")
      (footprint "eagle-import:0603")
      (fields (field (name "PACKAGE") "0603"))
      (libsource (lib "eagle-import") (part "RESISTOR0603"))
    )
    (comp (ref "R36")
      (value "10kΩ")
      (footprint "eagle-import:0603")
      (fields (field (name "PACKAGE") "0603"))
      (libsource (lib "eagle-import") (part "RESISTOR0603"))
    )
    (comp (ref "R37")
      (value "20kΩ 1%")
      (footprint "eagle-import:0603")
      (fields (field (name "PACKAGE") "0603"))
      (libsource (lib "eagle-import") (part "RESISTOR0603"))
    )
    (comp (ref "R38")
      (value "20kΩ")
      (footprint "eagle-import:0603")
      (fields (field (name "PACKAGE") "0603"))
      (libsource (lib "eagle-import") (part "RESISTOR0603"))
    )
    (comp (ref "SY")
      (value "OSHW-LOGOS")
      (footprint "eagle-import:OSHW-LOGO-S")
      (libsource (lib "eagle-import") (part "OSHW-LOGOS"))
    )
    (comp (ref "X1")
      (value "USB-MICROB")
      (footprint "eagle-import:USB-MICROB")
      (libsource (lib "eagle-import") (part "USB-MICROB"))
    )
    (comp (ref "X2")
      (value "ADC")
      (footprint "eagle-import:10POL254")
      (libsource (lib "eagle-import") (part "MPT10"))
    )
    (comp (ref "XTL1")
      (value "SMD3225-16MHZ 3.2 x 2.5mm crystal")
      (footprint "eagle-import:CRYSTAL-SMD-3X2")
      (libsource (lib "eagle-import") (part "CRYSTAL-GND3X2"))
    )
  )
  (nets
    (net (code "1") (name "+3.3V") (class "Default")
      (node (ref "C1") (pin "1") (pinfunction "1_1") (pintype "passive"))
      (node (ref "C12") (pin "1") (pinfunction "1_1") (pintype "passive"))
      (node (ref "C13") (pin "1") (pinfunction "1_1") (pintype "passive"))
      (node (ref "C14") (pin "1") (pinfunction "1_1") (pintype "passive"))
      (node (ref "C15") (pin "1") (pinfunction "1_1") (pintype "passive"))
      (node (ref "C18") (pin "2") (pinfunction "2_2") (pintype "passive"))
      (node (ref "C19") (pin "1") (pinfunction "1_1") (pintype "passive"))
      (node (ref "C2") (pin "1") (pinfunction "1_1") (pintype "passive"))
      (node (ref "C21") (pin "2") (pinfunction "2_2") (pintype "passive"))
      (node (ref "C22") (pin "2") (pinfunction "2_2") (pintype "passive"))
      (node (ref "C24") (pin "1") (pinfunction "1_1") (pintype "passive"))
      (node (ref "C25") (pin "1") (pinfunction "1_1") (pintype "passive"))
      (node (ref "C32") (pin "2") (pinfunction "2_2") (pintype "passive"))
      (node (ref "C33") (pin "2") (pinfunction "2_2") (pintype "passive"))
      (node (ref "C34") (pin "2") (pinfunction "2_2") (pintype "passive"))
      (node (ref "C35") (pin "2") (pinfunction "2_2") (pintype "passive"))
      (node (ref "C48") (pin "1") (pinfunction "1_1") (pintype "passive"))
      (node (ref "IC1") (pin "8") (pinfunction "VCC_8") (pintype "bidirectional"))
      (node (ref "IC10") (pin "2") (pinfunction "VS_2") (pintype "power_in"))
      (node (ref "IC11") (pin "8") (pinfunction "VDD/VREF_8") (pintype "input"))
      (node (ref "IC13") (pin "16") (pinfunction "VDD_RF_16") (pintype "power_in"))
      (node (ref "IC15") (pin "3") (pinfunction "VO_3") (pintype "passive"))
      (node (ref "IC3") (pin "2") (pinfunction "VCC_2") (pintype "bidirectional"))
      (node (ref "IC4") (pin "5") (pinfunction "V+_5") (pintype "bidirectional"))
      (node (ref "IC5") (pin "3") (pinfunction "VDDA_3") (pintype "bidirectional"))
      (node (ref "IC5") (pin "4") (pinfunction "VDDD_4") (pintype "bidirectional"))
      (node (ref "IC6") (pin "21") (pinfunction "VCC_21") (pintype "power_in"))
      (node (ref "IC6") (pin "52") (pinfunction "VCC1_52") (pintype "power_in"))
      (node (ref "IC6") (pin "64") (pinfunction "AVCC_64") (pintype "power_in"))
      (node (ref "IC7") (pin "13") (pinfunction "VDD_13") (pintype "bidirectional"))
      (node (ref "IC7") (pin "8") (pinfunction "VLOGIC_8") (pintype "bidirectional"))
      (node (ref "IC7") (pin "9") (pinfunction "AD0_9") (pintype "bidirectional"))
      (node (ref "IC8") (pin "8") (pinfunction "V+_8") (pintype "bidirectional"))
      (node (ref "IC9") (pin "22") (pinfunction "VDD_IO_22") (pintype "bidirectional"))
      (node (ref "IC9") (pin "23") (pinfunction "RES_23") (pintype "bidirectional"))
      (node (ref "IC9") (pin "6") (pinfunction "VDD_6") (pintype "bidirectional"))
      (node (ref "IC9") (pin "7") (pinfunction "RES_7") (pintype "bidirectional"))
      (node (ref "J1") (pin "4") (pinfunction "VDD_4") (pintype "power_in"))
      (node (ref "J2") (pin "2") (pinfunction "2_2") (pintype "passive"))
      (node (ref "J4") (pin "1") (pinfunction "S_1") (pintype "passive"))
      (node (ref "Q2") (pin "1") (pinfunction "G_1") (pintype "passive"))
      (node (ref "Q3") (pin "1") (pinfunction "G_1") (pintype "passive"))
      (node (ref "Q6") (pin "1") (pinfunction "G_1") (pintype "passive"))
      (node (ref "Q7") (pin "1") (pinfunction "G_1") (pintype "passive"))
      (node (ref "Q8") (pin "1") (pinfunction "G_1") (pintype "passive"))
      (node (ref "R1") (pin "1") (pinfunction "1_1") (pintype "passive"))
      (node (ref "R12") (pin "2") (pinfunction "2_2") (pintype "passive"))
      (node (ref "R15") (pin "2") (pinfunction "2_2") (pintype "passive"))
      (node (ref "R17") (pin "2") (pinfunction "2_2") (pintype "passive"))
      (node (ref "R2") (pin "1") (pinfunction "1_1") (pintype "passive"))
      (node (ref "R21") (pin "2") (pinfunction "2_2") (pintype "passive"))
      (node (ref "R24") (pin "2") (pinfunction "2_2") (pintype "passive"))
      (node (ref "R26") (pin "2") (pinfunction "2_2") (pintype "passive"))
      (node (ref "R3") (pin "2") (pinfunction "2_2") (pintype "passive"))
      (node (ref "R34") (pin "2") (pinfunction "2_2") (pintype "passive"))
      (node (ref "R8") (pin "2") (pinfunction "2_2") (pintype "passive"))
      (node (ref "R9") (pin "2") (pinfunction "2_2") (pintype "passive"))
    )
    (net (code "2") (name "+5V") (class "Default")
      (node (ref "C30") (pin "2") (pinfunction "2_2") (pintype "passive"))
      (node (ref "C36") (pin "1") (pinfunction "1_1") (pintype "passive"))
      (node (ref "C47") (pin "1") (pinfunction "1_1") (pintype "passive"))
      (node (ref "IC12") (pin "1") (pinfunction "VIN_1") (pintype "input"))
      (node (ref "IC14") (pin "16") (pinfunction "VDD_16") (pintype "bidirectional"))
      (node (ref "IC16") (pin "2") (pinfunction "VOUT_2") (pintype "passive"))
      (node (ref "J6") (pin "1") (pinfunction "S_1") (pintype "passive"))
      (node (ref "R13") (pin "2") (pinfunction "2_2") (pintype "passive"))
      (node (ref "R18") (pin "2") (pinfunction "2_2") (pintype "passive"))
      (node (ref "R22") (pin "2") (pinfunction "2_2") (pintype "passive"))
      (node (ref "R25") (pin "2") (pinfunction "2_2") (pintype "passive"))
      (node (ref "R27") (pin "2") (pinfunction "2_2") (pintype "passive"))
      (node (ref "R29") (pin "2") (pinfunction "2_2") (pintype "passive"))
      (node (ref "R30") (pin "2") (pinfunction "2_2") (pintype "passive"))
      (node (ref "R31") (pin "2") (pinfunction "2_2") (pintype "passive"))
      (node (ref "R32") (pin "2") (pinfunction "2_2") (pintype "passive"))
      (node (ref "R33") (pin "2") (pinfunction "2_2") (pintype "passive"))
    )
    (net (code "3") (name "/5V_MISO") (class "Default")
      (node (ref "IC14") (pin "12") (pinfunction "MISO_12") (pintype "bidirectional"))
      (node (ref "J6") (pin "3") (pinfunction "S_3") (pintype "passive"))
      (node (ref "Q6") (pin "3") (pinfunction "D_3") (pintype "passive"))
      (node (ref "R22") (pin "1") (pinfunction "1_1") (pintype "passive"))
    )
    (net (code "4") (name "/5V_MOSI") (class "Default")
      (node (ref "IC14") (pin "11") (pinfunction "MOSI_11") (pintype "bidirectional"))
      (node (ref "J6") (pin "4") (pinfunction "S_4") (pintype "passive"))
      (node (ref "Q7") (pin "3") (pinfunction "D_3") (pintype "passive"))
      (node (ref "R25") (pin "1") (pinfunction "1_1") (pintype "passive"))
    )
    (net (code "5") (name "/5V_SCK") (class "Default")
      (node (ref "IC14") (pin "13") (pinfunction "SCK_13") (pintype "bidirectional"))
      (node (ref "J6") (pin "5") (pinfunction "S_5") (pintype "passive"))
      (node (ref "Q3") (pin "3") (pinfunction "D_3") (pintype "passive"))
      (node (ref "R18") (pin "1") (pinfunction "1_1") (pintype "passive"))
    )
    (net (code "6") (name "/BATTERY_VOLTAGE") (class "Default")
      (node (ref "B2") (pin "+") (pinfunction "+_+") (pintype "bidirectional"))
      (node (ref "C49") (pin "1") (pinfunction "1_1") (pintype "passive"))
      (node (ref "IC17") (pin "5") (pinfunction "BAT_5") (pintype "passive"))
      (node (ref "J14") (pin "1") (pinfunction "1_1") (pintype "passive"))
      (node (ref "Q9") (pin "2") (pinfunction "S_2") (pintype "passive"))
      (node (ref "R14") (pin "2") (pinfunction "2_2") (pintype "passive"))
      (node (ref "R28") (pin "1") (pinfunction "1_1") (pintype "passive"))
    )
    (net (code "7") (name "/GPS_RXD") (class "Default")
      (node (ref "IC8") (pin "9") (pinfunction "NC1_9") (pintype "bidirectional"))
      (node (ref "J13") (pin "3") (pinfunction "S_3") (pintype "passive"))
    )
    (net (code "8") (name "/GPS_TXD") (class "Default")
      (node (ref "IC8") (pin "7") (pinfunction "NC2_7") (pintype "bidirectional"))
      (node (ref "J13") (pin "4") (pinfunction "S_4") (pintype "passive"))
    )
    (net (code "9") (name "/MICRO_RXD") (class "Default")
      (node (ref "IC6") (pin "27") (pinfunction "(RXD1/INT2)PD2_27") (pintype "bidirectional"))
      (node (ref "IC8") (pin "6") (pinfunction "COM2_6") (pintype "bidirectional"))
    )
    (net (code "10") (name "/MICRO_TXD") (class "Default")
      (node (ref "IC6") (pin "28") (pinfunction "(TXD1/INT3)PD3_28") (pintype "bidirectional"))
      (node (ref "IC8") (pin "10") (pinfunction "COM1_10") (pintype "bidirectional"))
    )
    (net (code "11") (name "/MISO") (class "Default")
      (node (ref "IC11") (pin "6") (pinfunction "DOUT_6") (pintype "input"))
      (node (ref "IC6") (pin "13") (pinfunction "(MISO/PCINT3)PB3_13") (pintype "bidirectional"))
      (node (ref "J1") (pin "7") (pinfunction "DATA_OUT_7") (pintype "output"))
      (node (ref "Q6") (pin "2") (pinfunction "S_2") (pintype "passive"))
      (node (ref "R21") (pin "1") (pinfunction "1_1") (pintype "passive"))
    )
    (net (code "12") (name "/MOSI") (class "Default")
      (node (ref "IC11") (pin "5") (pinfunction "DIN_5") (pintype "input"))
      (node (ref "IC6") (pin "12") (pinfunction "(MOSI/PCINT2)PB2_12") (pintype "bidirectional"))
      (node (ref "J1") (pin "3") (pinfunction "DATA_IN_3") (pintype "input"))
      (node (ref "Q7") (pin "2") (pinfunction "S_2") (pintype "passive"))
      (node (ref "R24") (pin "1") (pinfunction "1_1") (pintype "passive"))
    )
    (net (code "13") (name "/SCK") (class "Default")
      (node (ref "IC11") (pin "7") (pinfunction "CLK_7") (pintype "input"))
      (node (ref "IC6") (pin "11") (pinfunction "(SCK/PCINT1)PB1_11") (pintype "bidirectional"))
      (node (ref "J1") (pin "5") (pinfunction "SCLK_5") (pintype "input"))
      (node (ref "J2") (pin "3") (pinfunction "3_3") (pintype "passive"))
      (node (ref "Q3") (pin "2") (pinfunction "S_2") (pintype "passive"))
      (node (ref "R17") (pin "1") (pinfunction "1_1") (pintype "passive"))
    )
    (net (code "14") (name "/SCL") (class "Default")
      (node (ref "IC1") (pin "6") (pinfunction "SCL_6") (pintype "bidirectional"))
      (node (ref "IC4") (pin "1") (pinfunction "SCL_1") (pintype "bidirectional"))
      (node (ref "IC5") (pin "6") (pinfunction "SCL_6") (pintype "bidirectional"))
      (node (ref "IC6") (pin "25") (pinfunction "(SCL/INT0)PD0_25") (pintype "bidirectional"))
      (node (ref "IC7") (pin "23") (pinfunction "SCL_23") (pintype "bidirectional"))
      (node (ref "IC9") (pin "20") (pinfunction "SCL_M_20") (pintype "bidirectional"))
      (node (ref "IC9") (pin "24") (pinfunction "SCL_A_24") (pintype "bidirectional"))
      (node (ref "R8") (pin "1") (pinfunction "1_1") (pintype "passive"))
    )
    (net (code "15") (name "/SDA") (class "Default")
      (node (ref "IC1") (pin "5") (pinfunction "SDA_5") (pintype "bidirectional"))
      (node (ref "IC4") (pin "6") (pinfunction "SDA_6") (pintype "bidirectional"))
      (node (ref "IC5") (pin "7") (pinfunction "SDA_7") (pintype "bidirectional"))
      (node (ref "IC6") (pin "26") (pinfunction "(SDA/INT1)PD1_26") (pintype "bidirectional"))
      (node (ref "IC7") (pin "24") (pinfunction "SDA_24") (pintype "bidirectional"))
      (node (ref "IC9") (pin "19") (pinfunction "SDA_M_19") (pintype "bidirectional"))
      (node (ref "IC9") (pin "25") (pinfunction "SDA_A_25") (pintype "bidirectional"))
      (node (ref "R9") (pin "1") (pinfunction "1_1") (pintype "passive"))
    )
    (net (code "16") (name "/SI1000_RXD") (class "Default")
      (node (ref "IC13") (pin "31") (pinfunction "P0.5/RX_31") (pintype "bidirectional"))
      (node (ref "IC8") (pin "2") (pinfunction "NO1_2") (pintype "bidirectional"))
      (node (ref "J4") (pin "4") (pinfunction "S_4") (pintype "passive"))
    )
    (net (code "17") (name "/SI1000_TXD") (class "Default")
      (node (ref "IC13") (pin "32") (pinfunction "P0.4/TX_32") (pintype "bidirectional"))
      (node (ref "IC8") (pin "4") (pinfunction "NO2_4") (pintype "bidirectional"))
      (node (ref "J4") (pin "3") (pinfunction "S_3") (pintype "passive"))
    )
    (net (code "18") (name "/UART_SELECT") (class "Default")
      (node (ref "IC6") (pin "4") (pinfunction "(XCK0/AIN0)PE2_4") (pintype "bidirectional"))
      (node (ref "IC8") (pin "1") (pinfunction "IN1_1") (pintype "bidirectional"))
      (node (ref "IC8") (pin "5") (pinfunction "IN2_5") (pintype "bidirectional"))
      (node (ref "R11") (pin "2") (pinfunction "2_2") (pintype "passive"))
    )
    (net (code "19") (name "/USBVCC") (class "Default")
      (node (ref "C52") (pin "1") (pinfunction "1_1") (pintype "passive"))
      (node (ref "C7") (pin "1") (pinfunction "1_1") (pintype "passive"))
      (node (ref "C8") (pin "1") (pinfunction "1_1") (pintype "passive"))
      (node (ref "F1") (pin "2") (pinfunction "P$2_2") (pintype "bidirectional"))
      (node (ref "IC17") (pin "1") (pinfunction "USB_1") (pintype "input"))
      (node (ref "IC2") (pin "10") (pinfunction "VCC_10") (pintype "power_in"))
      (node (ref "IC2") (pin "9") (pinfunction "RESET#_9") (pintype "input"))
      (node (ref "LED2") (pin "A") (pinfunction "A_A") (pintype "passive"))
      (node (ref "LED3") (pin "A") (pinfunction "A_A") (pintype "passive"))
    )
    (net (code "20") (name "/USB_RXD") (class "Default")
      (node (ref "IC2") (pin "2") (pinfunction "RXD_2") (pintype "input"))
      (node (ref "IC6") (pin "3") (pinfunction "(TXD0/PDO)PE1_3") (pintype "bidirectional"))
      (node (ref "J2") (pin "1") (pinfunction "1_1") (pintype "passive"))
    )
    (net (code "21") (name "/USB_TXD") (class "Default")
      (node (ref "IC2") (pin "15") (pinfunction "TXD_15") (pintype "output"))
      (node (ref "IC6") (pin "2") (pinfunction "(RXD0/PCIN8/PDI)PE0_2") (pintype "bidirectional"))
      (node (ref "J2") (pin "4") (pinfunction "4_4") (pintype "passive"))
    )
    (net (code "22") (name "/VR_IF") (class "Default")
      (node (ref "IC13") (pin "20") (pinfunction "VR_IF_20") (pintype "power_in"))
    )
    (net (code "23") (name "/~{ACCEL_CS}") (class "Default")
      (node (ref "IC6") (pin "6") (pinfunction "(OC3B/INT4)PE4_6") (pintype "bidirectional"))
      (node (ref "Q2") (pin "2") (pinfunction "S_2") (pintype "passive"))
      (node (ref "R12") (pin "1") (pinfunction "1_1") (pintype "passive"))
    )
    (net (code "24") (name "/~{ADC2_CS}") (class "Default")
      (node (ref "IC11") (pin "1") (pinfunction "\\~{CS\\}/SHDN_1") (pintype "input"))
      (node (ref "IC6") (pin "29") (pinfunction "(ICP1)PD4_29") (pintype "bidirectional"))
      (node (ref "R15") (pin "1") (pinfunction "1_1") (pintype "passive"))
    )
    (net (code "25") (name "/~{ADC_CS}") (class "Default")
      (node (ref "IC6") (pin "9") (pinfunction "(CLKO/ICP3/INT7)PE7_9") (pintype "bidirectional"))
      (node (ref "Q8") (pin "2") (pinfunction "S_2") (pintype "passive"))
      (node (ref "R26") (pin "1") (pinfunction "1_1") (pintype "passive"))
    )
    (net (code "26") (name "/~{CARD}") (class "Default")
      (node (ref "IC6") (pin "8") (pinfunction "(T3/INT6)PE6_8") (pintype "bidirectional"))
      (node (ref "J1") (pin "CD1") (pinfunction "CARD_DETECT_CD1") (pintype "passive"))
      (node (ref "R1") (pin "2") (pinfunction "2_2") (pintype "passive"))
    )
    (net (code "27") (name "/~{LBO}") (class "Default")
      (node (ref "IC16") (pin "4") (pinfunction "LBO_4") (pintype "passive"))
      (node (ref "J16") (pin "2") (pinfunction "2_2") (pintype "passive"))
      (node (ref "LED7") (pin "C") (pinfunction "C_C") (pintype "passive"))
      (node (ref "R31") (pin "1") (pinfunction "1_1") (pintype "passive"))
    )
    (net (code "28") (name "/~{PGOOD}") (class "Default")
      (node (ref "IC16") (pin "8") (pinfunction "~{PGOOD}_8") (pintype "passive"))
      (node (ref "J16") (pin "1") (pinfunction "1_1") (pintype "passive"))
      (node (ref "R30") (pin "1") (pinfunction "1_1") (pintype "passive"))
    )
    (net (code "29") (name "/~{RESET}") (class "Default")
      (node (ref "C3") (pin "2") (pinfunction "2_2") (pintype "passive"))
      (node (ref "IC3") (pin "1") (pinfunction "RESET_1") (pintype "bidirectional"))
      (node (ref "IC6") (pin "20") (pinfunction "RESET_20") (pintype "input"))
      (node (ref "J2") (pin "5") (pinfunction "5_5") (pintype "passive"))
    )
    (net (code "30") (name "/~{SD_CS}") (class "Default")
      (node (ref "IC6") (pin "7") (pinfunction "(OC3C/INT5)PE5_7") (pintype "bidirectional"))
      (node (ref "J1") (pin "2") (pinfunction "CS_2") (pintype "input"))
      (node (ref "R2") (pin "2") (pinfunction "2_2") (pintype "passive"))
    )
    (net (code "31") (name "/~{SI1000_ENABLE}") (class "Default")
      (node (ref "IC13") (pin "15") (pinfunction "SDN_15") (pintype "bidirectional"))
      (node (ref "IC6") (pin "5") (pinfunction "(OC3A/AIN1)PE3_5") (pintype "bidirectional"))
      (node (ref "J4") (pin "2") (pinfunction "S_2") (pintype "passive"))
    )
    (net (code "32") (name "GND") (class "Default")
      (node (ref "B1") (pin "GND") (pinfunction "-_GND") (pintype "power_in"))
      (node (ref "B2") (pin "-") (pinfunction "-_-") (pintype "bidirectional"))
      (node (ref "C1") (pin "2") (pinfunction "2_2") (pintype "passive"))
      (node (ref "C10") (pin "2") (pinfunction "2_2") (pintype "passive"))
      (node (ref "C11") (pin "2") (pinfunction "2_2") (pintype "passive"))
      (node (ref "C12") (pin "2") (pinfunction "2_2") (pintype "passive"))
      (node (ref "C13") (pin "2") (pinfunction "2_2") (pintype "passive"))
      (node (ref "C14") (pin "2") (pinfunction "2_2") (pintype "passive"))
      (node (ref "C15") (pin "2") (pinfunction "2_2") (pintype "passive"))
      (node (ref "C16") (pin "2") (pinfunction "2_2") (pintype "passive"))
      (node (ref "C17") (pin "2") (pinfunction "2_2") (pintype "passive"))
      (node (ref "C18") (pin "1") (pinfunction "1_1") (pintype "passive"))
      (node (ref "C19") (pin "2") (pinfunction "2_2") (pintype "passive"))
      (node (ref "C2") (pin "2") (pinfunction "2_2") (pintype "passive"))
      (node (ref "C20") (pin "2") (pinfunction "2_2") (pintype "passive"))
      (node (ref "C21") (pin "1") (pinfunction "1_1") (pintype "passive"))
      (node (ref "C22") (pin "1") (pinfunction "1_1") (pintype "passive"))
      (node (ref "C23") (pin "2") (pinfunction "2_2") (pintype "passive"))
      (node (ref "C24") (pin "2") (pinfunction "2_2") (pintype "passive"))
      (node (ref "C25") (pin "2") (pinfunction "2_2") (pintype "passive"))
      (node (ref "C27") (pin "2") (pinfunction "2_2") (pintype "passive"))
      (node (ref "C28") (pin "2") (pinfunction "2_2") (pintype "passive"))
      (node (ref "C29") (pin "2") (pinfunction "2_2") (pintype "passive"))
      (node (ref "C30") (pin "1") (pinfunction "1_1") (pintype "passive"))
      (node (ref "C31") (pin "2") (pinfunction "2_2") (pintype "passive"))
      (node (ref "C32") (pin "1") (pinfunction "1_1") (pintype "passive"))
      (node (ref "C33") (pin "1") (pinfunction "1_1") (pintype "passive"))
      (node (ref "C34") (pin "1") (pinfunction "1_1") (pintype "passive"))
      (node (ref "C35") (pin "1") (pinfunction "1_1") (pintype "passive"))
      (node (ref "C36") (pin "2") (pinfunction "2_2") (pintype "passive"))
      (node (ref "C39") (pin "2") (pinfunction "2_2") (pintype "passive"))
      (node (ref "C4") (pin "2") (pinfunction "2_2") (pintype "passive"))
      (node (ref "C40") (pin "2") (pinfunction "2_2") (pintype "passive"))
      (node (ref "C41") (pin "1") (pinfunction "1_1") (pintype "passive"))
      (node (ref "C42") (pin "1") (pinfunction "1_1") (pintype "passive"))
      (node (ref "C43") (pin "1") (pinfunction "1_1") (pintype "passive"))
      (node (ref "C44") (pin "1") (pinfunction "1_1") (pintype "passive"))
      (node (ref "C45") (pin "1") (pinfunction "1_1") (pintype "passive"))
      (node (ref "C46") (pin "1") (pinfunction "1_1") (pintype "passive"))
      (node (ref "C47") (pin "2") (pinfunction "2_2") (pintype "passive"))
      (node (ref "C48") (pin "2") (pinfunction "2_2") (pintype "passive"))
      (node (ref "C49") (pin "2") (pinfunction "2_2") (pintype "passive"))
      (node (ref "C5") (pin "2") (pinfunction "2_2") (pintype "passive"))
      (node (ref "C50") (pin "2") (pinfunction "2_2") (pintype "passive"))
      (node (ref "C51") (pin "2") (pinfunction "2_2") (pintype "passive"))
      (node (ref "C52") (pin "2") (pinfunction "2_2") (pintype "passive"))
      (node (ref "C53") (pin "2") (pinfunction "2_2") (pintype "passive"))
      (node (ref "C54") (pin "2") (pinfunction "2_2") (pintype "passive"))
      (node (ref "C6") (pin "2") (pinfunction "2_2") (pintype "passive"))
      (node (ref "C7") (pin "2") (pinfunction "2_2") (pintype "passive"))
      (node (ref "C8") (pin "2") (pinfunction "2_2") (pintype "passive"))
      (node (ref "C9") (pin "2") (pinfunction "2_2") (pintype "passive"))
      (node (ref "IC1") (pin "4") (pinfunction "GND_4") (pintype "bidirectional"))
      (node (ref "IC10") (pin "3") (pinfunction "GND_3") (pintype "power_in"))
      (node (ref "IC11") (pin "4") (pinfunction "VSS_4") (pintype "input"))
      (node (ref "IC12") (pin "3") (pinfunction "GND_3") (pintype "passive"))
      (node (ref "IC13") (pin "23") (pinfunction "GND2_23") (pintype "power_in"))
      (node (ref "IC13") (pin "37") (pinfunction "GND4_37") (pintype "power_in"))
      (node (ref "IC13") (pin "EP1") (pinfunction "GND5_EP1") (pintype "power_in"))
      (node (ref "IC13") (pin "EP2") (pinfunction "GND6_EP2") (pintype "power_in"))
      (node (ref "IC13") (pin "EP3") (pinfunction "GND7_EP3") (pintype "power_in"))
      (node (ref "IC13") (pin "EP4") (pinfunction "GND8_EP4") (pintype "power_in"))
      (node (ref "IC13") (pin "EP5") (pinfunction "GND9_EP5") (pintype "power_in"))
      (node (ref "IC13") (pin "EP6") (pinfunction "GND10_EP6") (pintype "power_in"))
      (node (ref "IC13") (pin "EP7") (pinfunction "GND11_EP7") (pintype "power_in"))
      (node (ref "IC13") (pin "EP8") (pinfunction "GND12_EP8") (pintype "power_in"))
      (node (ref "IC13") (pin "P$1") (pinfunction "EP_UC_P$1") (pintype "power_in"))
      (node (ref "IC13") (pin "P$2") (pinfunction "EP_RF_P$2") (pintype "power_in"))
      (node (ref "IC14") (pin "14") (pinfunction "AGND_14") (pintype "bidirectional"))
      (node (ref "IC14") (pin "9") (pinfunction "DGND_9") (pintype "bidirectional"))
      (node (ref "IC15") (pin "4") (pinfunction "GND_4") (pintype "passive"))
      (node (ref "IC16") (pin "10") (pinfunction "PGND_10") (pintype "power_in"))
      (node (ref "IC16") (pin "5") (pinfunction "GND_5") (pintype "power_in"))
      (node (ref "IC16") (pin "EXP") (pinfunction "EXP_EXP") (pintype "power_in"))
      (node (ref "IC17") (pin "2") (pinfunction "GND_2") (pintype "power_in"))
      (node (ref "IC18") (pin "4") (pinfunction "GND_4") (pintype "passive"))
      (node (ref "IC2") (pin "13") (pinfunction "GND2_13") (pintype "power_in"))
      (node (ref "IC2") (pin "3") (pinfunction "GND1_3") (pintype "power_in"))
      (node (ref "IC2") (pin "C") (pinfunction "GND3_C") (pintype "power_in"))
      (node (ref "IC3") (pin "3") (pinfunction "GND_3") (pintype "bidirectional"))
      (node (ref "IC4") (pin "2") (pinfunction "GND_2") (pintype "bidirectional"))
      (node (ref "IC4") (pin "4") (pinfunction "ADD0_4") (pintype "bidirectional"))
      (node (ref "IC5") (pin "1") (pinfunction "GND_1") (pintype "bidirectional"))
      (node (ref "IC6") (pin "22") (pinfunction "GND_22") (pintype "power_in"))
      (node (ref "IC6") (pin "53") (pinfunction "GND1_53") (pintype "power_in"))
      (node (ref "IC6") (pin "63") (pinfunction "AGND_63") (pintype "power_in"))
      (node (ref "IC6") (pin "TGND1") (pinfunction "TGND1_TGND1") (pintype "power_in"))
      (node (ref "IC6") (pin "TGND2") (pinfunction "TGND2_TGND2") (pintype "power_in"))
      (node (ref "IC6") (pin "TGND3") (pinfunction "TGND3_TGND3") (pintype "power_in"))
      (node (ref "IC6") (pin "TGND4") (pinfunction "TGND4_TGND4") (pintype "power_in"))
      (node (ref "IC7") (pin "1") (pinfunction "CLKIN_1") (pintype "bidirectional"))
      (node (ref "IC7") (pin "11") (pinfunction "RESV-G_11") (pintype "bidirectional"))
      (node (ref "IC7") (pin "18") (pinfunction "GND_18") (pintype "bidirectional"))
      (node (ref "IC8") (pin "3") (pinfunction "GND_3") (pintype "bidirectional"))
      (node (ref "IC9") (pin "1") (pinfunction "RES_1") (pintype "bidirectional"))
      (node (ref "IC9") (pin "17") (pinfunction "RES_17") (pintype "bidirectional"))
      (node (ref "IC9") (pin "2") (pinfunction "GND_2") (pintype "bidirectional"))
      (node (ref "IC9") (pin "28") (pinfunction "RES_28") (pintype "bidirectional"))
      (node (ref "IC9") (pin "3") (pinfunction "RES_3") (pintype "bidirectional"))
      (node (ref "IC9") (pin "4") (pinfunction "SA0_A_4") (pintype "bidirectional"))
      (node (ref "J1") (pin "6") (pinfunction "VSS_6") (pintype "power_in"))
      (node (ref "J1") (pin "MT1") (pinfunction "GND_MT1") (pintype "power_in"))
      (node (ref "J1") (pin "MT2") (pinfunction "GND1_MT2") (pintype "power_in"))
      (node (ref "J13") (pin "2") (pinfunction "S_2") (pintype "passive"))
      (node (ref "J2") (pin "6") (pinfunction "6_6") (pintype "passive"))
      (node (ref "J4") (pin "5") (pinfunction "S_5") (pintype "passive"))
      (node (ref "J6") (pin "2") (pinfunction "S_2") (pintype "passive"))
      (node (ref "J8") (pin "G@1") (pinfunction "GND_G@1") (pintype "power_in"))
      (node (ref "J8") (pin "G@2") (pinfunction "GND_G@2") (pintype "power_in"))
      (node (ref "J8") (pin "G@3") (pinfunction "GND_G@3") (pintype "power_in"))
      (node (ref "J8") (pin "G@4") (pinfunction "GND_G@4") (pintype "power_in"))
      (node (ref "LED5") (pin "C") (pinfunction "C_C") (pintype "passive"))
      (node (ref "LED6") (pin "C") (pinfunction "C_C") (pintype "passive"))
      (node (ref "R11") (pin "1") (pinfunction "1_1") (pintype "passive"))
      (node (ref "R16") (pin "1") (pinfunction "1_1") (pintype "passive"))
      (node (ref "R36") (pin "1") (pinfunction "1_1") (pintype "passive"))
      (node (ref "R37") (pin "1") (pinfunction "1_1") (pintype "passive"))
      (node (ref "R38") (pin "1") (pinfunction "1_1") (pintype "passive"))
      (node (ref "X2") (pin "10") (pinfunction "1_10") (pintype "passive"))
      (node (ref "X2") (pin "9") (pinfunction "1_9") (pintype "passive"))
      (node (ref "XTL1") (pin "2") (pinfunction "GND_2") (pintype "bidirectional"))
      (node (ref "XTL1") (pin "4") (pinfunction "GND2_4") (pintype "bidirectional"))
    )
    (net (code "33") (name "Net-(B1-+)") (class "Default")
      (node (ref "B1") (pin "PWR@1") (pinfunction "+_PWR@1") (pintype "power_in"))
      (node (ref "IC1") (pin "3") (pinfunction "VBATT_3") (pintype "bidirectional"))
    )
    (net (code "34") (name "Net-(C4-Pad1)") (class "Default")
      (node (ref "C4") (pin "1") (pinfunction "1_1") (pintype "passive"))
      (node (ref "R4") (pin "1") (pinfunction "1_1") (pintype "passive"))
      (node (ref "X1") (pin "D-") (pinfunction "D-_D-") (pintype "bidirectional"))
    )
    (net (code "35") (name "Net-(C5-Pad1)") (class "Default")
      (node (ref "C5") (pin "1") (pinfunction "1_1") (pintype "passive"))
      (node (ref "R7") (pin "1") (pinfunction "1_1") (pintype "passive"))
      (node (ref "X1") (pin "D+") (pinfunction "D+_D+") (pintype "bidirectional"))
    )
    (net (code "36") (name "Net-(C27-Pad1)") (class "Default")
      (node (ref "C27") (pin "1") (pinfunction "1_1") (pintype "passive"))
      (node (ref "J8") (pin "1") (pinfunction "1_1") (pintype "passive"))
      (node (ref "L1") (pin "1") (pinfunction "1_1") (pintype "passive"))
    )
    (net (code "37") (name "Net-(C28-Pad1)") (class "Default")
      (node (ref "C28") (pin "1") (pinfunction "1_1") (pintype "passive"))
      (node (ref "L1") (pin "2") (pinfunction "2_2") (pintype "passive"))
      (node (ref "L2") (pin "1") (pinfunction "1_1") (pintype "passive"))
    )
    (net (code "38") (name "Net-(C29-Pad1)") (class "Default")
      (node (ref "C29") (pin "1") (pinfunction "1_1") (pintype "passive"))
      (node (ref "L2") (pin "2") (pinfunction "2_2") (pintype "passive"))
      (node (ref "L3") (pin "1") (pinfunction "1_1") (pintype "passive"))
    )
    (net (code "39") (name "Net-(C37-Pad2)") (class "Default")
      (node (ref "C37") (pin "2") (pinfunction "2_2") (pintype "passive"))
      (node (ref "L6") (pin "2") (pinfunction "2_2") (pintype "passive"))
    )
    (net (code "40") (name "Net-(C38-Pad1)") (class "Default")
      (node (ref "C38") (pin "1") (pinfunction "1_1") (pintype "passive"))
      (node (ref "C39") (pin "1") (pinfunction "1_1") (pintype "passive"))
      (node (ref "L3") (pin "2") (pinfunction "2_2") (pintype "passive"))
      (node (ref "L6") (pin "1") (pinfunction "1_1") (pintype "passive"))
      (node (ref "L8") (pin "2") (pinfunction "2_2") (pintype "passive"))
    )
    (net (code "41") (name "Net-(F1-P$1)") (class "Default")
      (node (ref "F1") (pin "1") (pinfunction "P$1_1") (pintype "bidirectional"))
      (node (ref "X1") (pin "VBUS") (pinfunction "VBUS_VBUS") (pintype "bidirectional"))
    )
    (net (code "42") (name "Net-(IC1-SQW)") (class "Default")
      (node (ref "IC1") (pin "7") (pinfunction "SQW_7") (pintype "bidirectional"))
      (node (ref "LED1") (pin "C") (pinfunction "C_C") (pintype "passive"))
    )
    (net (code "43") (name "Net-(IC1-X1)") (class "Default")
      (node (ref "IC1") (pin "1") (pinfunction "X1_1") (pintype "bidirectional"))
      (node (ref "Q1") (pin "X1") (pinfunction "1_X1") (pintype "passive"))
    )
    (net (code "44") (name "Net-(IC1-X2)") (class "Default")
      (node (ref "IC1") (pin "2") (pinfunction "X2_2") (pintype "bidirectional"))
      (node (ref "Q1") (pin "X2") (pinfunction "2_X2") (pintype "passive"))
    )
    (net (code "45") (name "Net-(IC2-3V3OUT)") (class "Default")
      (node (ref "C6") (pin "1") (pinfunction "1_1") (pintype "passive"))
      (node (ref "IC2") (pin "1") (pinfunction "VCCIO_1") (pintype "input"))
      (node (ref "IC2") (pin "8") (pinfunction "3V3OUT_8") (pintype "output"))
    )
    (net (code "46") (name "Net-(IC2-CBUS1)") (class "Default")
      (node (ref "IC2") (pin "11") (pinfunction "CBUS1_11") (pintype "bidirectional"))
      (node (ref "R5") (pin "1") (pinfunction "1_1") (pintype "passive"))
    )
    (net (code "47") (name "Net-(IC2-CBUS2)") (class "Default")
      (node (ref "IC2") (pin "5") (pinfunction "CBUS2_5") (pintype "bidirectional"))
      (node (ref "R6") (pin "1") (pinfunction "1_1") (pintype "passive"))
    )
    (net (code "48") (name "Net-(IC2-CTS#)") (class "Default")
      (node (ref "C3") (pin "1") (pinfunction "1_1") (pintype "passive"))
      (node (ref "IC2") (pin "4") (pinfunction "CTS#_4") (pintype "bidirectional"))
    )
    (net (code "49") (name "Net-(IC2-USBDM)") (class "Default")
      (node (ref "IC2") (pin "7") (pinfunction "USBDM_7") (pintype "bidirectional"))
      (node (ref "R4") (pin "2") (pinfunction "2_2") (pintype "passive"))
    )
    (net (code "50") (name "Net-(IC2-USBDP)") (class "Default")
      (node (ref "IC2") (pin "6") (pinfunction "USBDP_6") (pintype "bidirectional"))
      (node (ref "R7") (pin "2") (pinfunction "2_2") (pintype "passive"))
    )
    (net (code "51") (name "Net-(IC5-EOC)") (class "Default")
      (node (ref "IC5") (pin "2") (pinfunction "EOC_2") (pintype "bidirectional"))
      (node (ref "J3") (pin "1") (pinfunction "1_1") (pintype "passive"))
    )
    (net (code "52") (name "Net-(IC5-XCLR)") (class "Default")
      (node (ref "IC5") (pin "8") (pinfunction "XCLR_8") (pintype "bidirectional"))
      (node (ref "J3") (pin "2") (pinfunction "2_2") (pintype "passive"))
    )
    (net (code "53") (name "Net-(IC6-AREF)") (class "Default")
      (node (ref "C11") (pin "1") (pinfunction "1_1") (pintype "passive"))
      (node (ref "IC6") (pin "62") (pinfunction "AREF_62") (pintype "bidirectional"))
    )
    (net (code "54") (name "Net-(IC6-XTAL1)") (class "Default")
      (node (ref "C9") (pin "1") (pinfunction "1_1") (pintype "passive"))
      (node (ref "IC6") (pin "24") (pinfunction "XTAL1_24") (pintype "input"))
      (node (ref "R10") (pin "2") (pinfunction "2_2") (pintype "passive"))
      (node (ref "XTL1") (pin "3") (pinfunction "XTL2_3") (pintype "bidirectional"))
    )
    (net (code "55") (name "Net-(IC6-XTAL2)") (class "Default")
      (node (ref "C10") (pin "1") (pinfunction "1_1") (pintype "passive"))
      (node (ref "IC6") (pin "23") (pinfunction "XTAL2_23") (pintype "output"))
      (node (ref "R10") (pin "1") (pinfunction "1_1") (pintype "passive"))
      (node (ref "XTL1") (pin "1") (pinfunction "XTL1_1") (pintype "bidirectional"))
    )
    (net (code "56") (name "Net-(IC7-CPOUT)") (class "Default")
      (node (ref "C17") (pin "1") (pinfunction "1_1") (pintype "passive"))
      (node (ref "IC7") (pin "20") (pinfunction "CPOUT_20") (pintype "bidirectional"))
    )
    (net (code "57") (name "Net-(IC7-INT)") (class "Default")
      (node (ref "IC7") (pin "12") (pinfunction "INT_12") (pintype "bidirectional"))
      (node (ref "J5") (pin "1") (pinfunction "1_1") (pintype "passive"))
    )
    (net (code "58") (name "Net-(IC7-REGOUT)") (class "Default")
      (node (ref "C16") (pin "1") (pinfunction "1_1") (pintype "passive"))
      (node (ref "IC7") (pin "10") (pinfunction "REGOUT_10") (pintype "bidirectional"))
    )
    (net (code "59") (name "Net-(IC9-C1)") (class "Default")
      (node (ref "C20") (pin "1") (pinfunction "1_1") (pintype "passive"))
      (node (ref "IC9") (pin "15") (pinfunction "C1_15") (pintype "bidirectional"))
    )
    (net (code "60") (name "Net-(IC9-DRDY_M)") (class "Default")
      (node (ref "IC9") (pin "18") (pinfunction "DRDY_M_18") (pintype "bidirectional"))
      (node (ref "J7") (pin "3") (pinfunction "3_3") (pintype "passive"))
    )
    (net (code "61") (name "Net-(IC9-INT1)") (class "Default")
      (node (ref "IC9") (pin "26") (pinfunction "INT1_26") (pintype "bidirectional"))
      (node (ref "J7") (pin "1") (pinfunction "1_1") (pintype "passive"))
    )
    (net (code "62") (name "Net-(IC9-INT2)") (class "Default")
      (node (ref "IC9") (pin "27") (pinfunction "INT2_27") (pintype "bidirectional"))
      (node (ref "J7") (pin "2") (pinfunction "2_2") (pintype "passive"))
    )
    (net (code "63") (name "Net-(IC9-SET1)") (class "Default")
      (node (ref "C26") (pin "2") (pinfunction "2_2") (pintype "passive"))
      (node (ref "IC9") (pin "16") (pinfunction "SET1_16") (pintype "bidirectional"))
    )
    (net (code "64") (name "Net-(IC9-SET2)") (class "Default")
      (node (ref "C26") (pin "1") (pinfunction "1_1") (pintype "passive"))
      (node (ref "IC9") (pin "12") (pinfunction "SET2_12") (pintype "bidirectional"))
    )
    (net (code "65") (name "Net-(IC10-VOUT)") (class "Default")
      (node (ref "C23") (pin "1") (pinfunction "1_1") (pintype "passive"))
      (node (ref "IC10") (pin "4") (pinfunction "VOUT_4") (pintype "output"))
      (node (ref "IC11") (pin "3") (pinfunction "CH1_3") (pintype "input"))
    )
    (net (code "66") (name "Net-(IC11-CH0)") (class "Default")
      (node (ref "IC11") (pin "2") (pinfunction "CH0_2") (pintype "input"))
      (node (ref "R14") (pin "1") (pinfunction "1_1") (pintype "passive"))
      (node (ref "R16") (pin "2") (pinfunction "2_2") (pintype "passive"))
    )
    (net (code "67") (name "Net-(IC12-VO)") (class "Default")
      (node (ref "C31") (pin "1") (pinfunction "1_1") (pintype "passive"))
      (node (ref "IC12") (pin "2") (pinfunction "VO_2") (pintype "output"))
      (node (ref "IC14") (pin "15") (pinfunction "VREF_15") (pintype "bidirectional"))
    )
    (net (code "68") (name "Net-(IC13-GPIO_0)") (class "Default")
      (node (ref "IC13") (pin "24") (pinfunction "GPIO_0_24") (pintype "bidirectional"))
      (node (ref "J12") (pin "3") (pinfunction "3_3") (pintype "passive"))
    )
    (net (code "69") (name "Net-(IC13-GPIO_1)") (class "Default")
      (node (ref "IC13") (pin "25") (pinfunction "GPIO_1_25") (pintype "bidirectional"))
      (node (ref "J12") (pin "2") (pinfunction "2_2") (pintype "passive"))
    )
    (net (code "70") (name "Net-(IC13-GPIO_2)") (class "Default")
      (node (ref "IC13") (pin "26") (pinfunction "GPIO_2_26") (pintype "bidirectional"))
      (node (ref "J12") (pin "1") (pinfunction "1_1") (pintype "passive"))
    )
    (net (code "71") (name "Net-(IC13-NIRQ)") (class "Default")
      (node (ref "IC13") (pin "10") (pinfunction "P1.5_10") (pintype "bidirectional"))
      (node (ref "IC13") (pin "11") (pinfunction "NIRQ_11") (pintype "bidirectional"))
      (node (ref "R19") (pin "1") (pinfunction "1_1") (pintype "passive"))
    )
    (net (code "72") (name "Net-(IC13-NRST{slash}C2CK)") (class "Default")
      (node (ref "IC13") (pin "39") (pinfunction "NRST/C2CK_39") (pintype "bidirectional"))
      (node (ref "J10") (pin "2") (pinfunction "2_2") (pintype "passive"))
      (node (ref "R23") (pin "1") (pinfunction "1_1") (pintype "passive"))
    )
    (net (code "73") (name "Net-(IC13-P0.0{slash}VREF)") (class "Default")
      (node (ref "C46") (pin "2") (pinfunction "2_2") (pintype "passive"))
      (node (ref "IC13") (pin "36") (pinfunction "P0.0/VREF_36") (pintype "bidirectional"))
      (node (ref "J10") (pin "3") (pinfunction "3_3") (pintype "passive"))
    )
    (net (code "74") (name "Net-(IC13-P0.6{slash}CNVSTR)") (class "Default")
      (node (ref "IC13") (pin "30") (pinfunction "P0.6/CNVSTR_30") (pintype "bidirectional"))
      (node (ref "J11") (pin "1") (pinfunction "1_1") (pintype "passive"))
    )
    (net (code "75") (name "Net-(IC13-P0.7{slash}IREF0)") (class "Default")
      (node (ref "IC13") (pin "29") (pinfunction "P0.7/IREF0_29") (pintype "bidirectional"))
      (node (ref "J11") (pin "2") (pinfunction "2_2") (pintype "passive"))
    )
    (net (code "76") (name "Net-(IC13-P1.6)") (class "Default")
      (node (ref "IC13") (pin "9") (pinfunction "P1.6_9") (pintype "bidirectional"))
      (node (ref "J9") (pin "1") (pinfunction "1_1") (pintype "passive"))
    )
    (net (code "77") (name "Net-(IC13-P1.7)") (class "Default")
      (node (ref "IC13") (pin "8") (pinfunction "P1.7_8") (pintype "bidirectional"))
      (node (ref "J9") (pin "2") (pinfunction "2_2") (pintype "passive"))
    )
    (net (code "78") (name "Net-(IC13-P2.0)") (class "Default")
      (node (ref "IC13") (pin "7") (pinfunction "P2.0_7") (pintype "bidirectional"))
      (node (ref "J9") (pin "3") (pinfunction "3_3") (pintype "passive"))
    )
    (net (code "79") (name "Net-(IC13-P2.1)") (class "Default")
      (node (ref "IC13") (pin "6") (pinfunction "P2.1_6") (pintype "bidirectional"))
      (node (ref "J9") (pin "4") (pinfunction "4_4") (pintype "passive"))
    )
    (net (code "80") (name "Net-(IC13-P2.2)") (class "Default")
      (node (ref "IC13") (pin "5") (pinfunction "P2.2_5") (pintype "bidirectional"))
      (node (ref "J9") (pin "5") (pinfunction "5_5") (pintype "passive"))
    )
    (net (code "81") (name "Net-(IC13-P2.3)") (class "Default")
      (node (ref "IC13") (pin "4") (pinfunction "P2.3_4") (pintype "bidirectional"))
      (node (ref "J9") (pin "6") (pinfunction "6_6") (pintype "passive"))
    )
    (net (code "82") (name "Net-(IC13-P2.4)") (class "Default")
      (node (ref "IC13") (pin "3") (pinfunction "P2.4_3") (pintype "bidirectional"))
      (node (ref "J9") (pin "7") (pinfunction "7_7") (pintype "passive"))
    )
    (net (code "83") (name "Net-(IC13-P2.5)") (class "Default")
      (node (ref "IC13") (pin "2") (pinfunction "P2.5_2") (pintype "bidirectional"))
      (node (ref "J9") (pin "8") (pinfunction "8_8") (pintype "passive"))
    )
    (net (code "84") (name "Net-(IC13-P2.7{slash}C2D)") (class "Default")
      (node (ref "IC13") (pin "40") (pinfunction "P2.7/C2D_40") (pintype "bidirectional"))
      (node (ref "J10") (pin "1") (pinfunction "1_1") (pintype "passive"))
    )
    (net (code "85") (name "Net-(IC13-RXN)") (class "Default")
      (node (ref "C40") (pin "1") (pinfunction "1_1") (pintype "passive"))
      (node (ref "IC13") (pin "19") (pinfunction "RXN_19") (pintype "bidirectional"))
      (node (ref "L7") (pin "1") (pinfunction "1_1") (pintype "passive"))
      (node (ref "L8") (pin "1") (pinfunction "1_1") (pintype "passive"))
    )
    (net (code "86") (name "Net-(IC13-RXP)") (class "Default")
      (node (ref "C38") (pin "2") (pinfunction "2_2") (pintype "passive"))
      (node (ref "IC13") (pin "18") (pinfunction "RXP_18") (pintype "bidirectional"))
      (node (ref "L7") (pin "2") (pinfunction "2_2") (pintype "passive"))
    )
    (net (code "87") (name "Net-(IC13-TX)") (class "Default")
      (node (ref "C37") (pin "1") (pinfunction "1_1") (pintype "passive"))
      (node (ref "IC13") (pin "17") (pinfunction "TX_17") (pintype "bidirectional"))
      (node (ref "L5") (pin "1") (pinfunction "1_1") (pintype "passive"))
    )
    (net (code "88") (name "Net-(IC13-VDD_DIG)") (class "Default")
      (node (ref "C43") (pin "2") (pinfunction "2_2") (pintype "passive"))
      (node (ref "C44") (pin "2") (pinfunction "2_2") (pintype "passive"))
      (node (ref "C45") (pin "2") (pinfunction "2_2") (pintype "passive"))
      (node (ref "IC13") (pin "28") (pinfunction "VDD_DIG_28") (pintype "power_in"))
      (node (ref "IC13") (pin "38") (pinfunction "VDD_MCU_38") (pintype "power_in"))
      (node (ref "L4") (pin "1") (pinfunction "1_1") (pintype "passive"))
      (node (ref "R19") (pin "2") (pinfunction "2_2") (pintype "passive"))
      (node (ref "R23") (pin "2") (pinfunction "2_2") (pintype "passive"))
    )
    (net (code "89") (name "Net-(IC13-VDR)") (class "Default")
      (node (ref "C41") (pin "2") (pinfunction "2_2") (pintype "passive"))
      (node (ref "C42") (pin "2") (pinfunction "2_2") (pintype "passive"))
      (node (ref "IC13") (pin "27") (pinfunction "VDR_27") (pintype "power_in"))
    )
    (net (code "90") (name "Net-(IC13-XIN)") (class "Default")
      (node (ref "IC13") (pin "13") (pinfunction "XIN_13") (pintype "bidirectional"))
      (node (ref "Q4") (pin "1") (pinfunction "1_1") (pintype "passive"))
    )
    (net (code "91") (name "Net-(IC13-XOUT)") (class "Default")
      (node (ref "IC13") (pin "12") (pinfunction "XOUT_12") (pintype "bidirectional"))
      (node (ref "Q4") (pin "3") (pinfunction "2_3") (pintype "passive"))
    )
    (net (code "92") (name "Net-(IC13-XTAL3)") (class "Default")
      (node (ref "IC13") (pin "1") (pinfunction "XTAL3_1") (pintype "bidirectional"))
      (node (ref "Q5") (pin "X2") (pinfunction "2_X2") (pintype "passive"))
    )
    (net (code "93") (name "Net-(IC13-XTAL4)") (class "Default")
      (node (ref "IC13") (pin "42") (pinfunction "XTAL4_42") (pintype "bidirectional"))
      (node (ref "Q5") (pin "X1") (pinfunction "1_X1") (pintype "passive"))
    )
    (net (code "94") (name "Net-(IC14-IN0)") (class "Default")
      (node (ref "IC14") (pin "1") (pinfunction "IN0_1") (pintype "bidirectional"))
      (node (ref "X2") (pin "1") (pinfunction "1_1") (pintype "passive"))
    )
    (net (code "95") (name "Net-(IC14-IN1)") (class "Default")
      (node (ref "IC14") (pin "2") (pinfunction "IN1_2") (pintype "bidirectional"))
      (node (ref "X2") (pin "2") (pinfunction "1_2") (pintype "passive"))
    )
    (net (code "96") (name "Net-(IC14-IN2)") (class "Default")
      (node (ref "IC14") (pin "3") (pinfunction "IN2_3") (pintype "bidirectional"))
      (node (ref "X2") (pin "3") (pinfunction "1_3") (pintype "passive"))
    )
    (net (code "97") (name "Net-(IC14-IN3)") (class "Default")
      (node (ref "IC14") (pin "4") (pinfunction "IN3_4") (pintype "bidirectional"))
      (node (ref "X2") (pin "4") (pinfunction "1_4") (pintype "passive"))
    )
    (net (code "98") (name "Net-(IC14-IN4)") (class "Default")
      (node (ref "IC14") (pin "5") (pinfunction "IN4_5") (pintype "bidirectional"))
      (node (ref "X2") (pin "5") (pinfunction "1_5") (pintype "passive"))
    )
    (net (code "99") (name "Net-(IC14-IN5)") (class "Default")
      (node (ref "IC14") (pin "6") (pinfunction "IN5_6") (pintype "bidirectional"))
      (node (ref "X2") (pin "6") (pinfunction "1_6") (pintype "passive"))
    )
    (net (code "100") (name "Net-(IC14-IN6)") (class "Default")
      (node (ref "IC14") (pin "7") (pinfunction "IN6_7") (pintype "bidirectional"))
      (node (ref "X2") (pin "7") (pinfunction "1_7") (pintype "passive"))
    )
    (net (code "101") (name "Net-(IC14-IN7)") (class "Default")
      (node (ref "IC14") (pin "8") (pinfunction "IN7_8") (pintype "bidirectional"))
      (node (ref "X2") (pin "8") (pinfunction "1_8") (pintype "passive"))
    )
    (net (code "102") (name "Net-(IC14-{slash}CS)") (class "Default")
      (node (ref "IC14") (pin "10") (pinfunction "/CS_10") (pintype "bidirectional"))
      (node (ref "Q8") (pin "3") (pinfunction "D_3") (pintype "passive"))
      (node (ref "R27") (pin "1") (pinfunction "1_1") (pintype "passive"))
    )
    (net (code "103") (name "Net-(IC15-VI)") (class "Default")
      (node (ref "C50") (pin "1") (pinfunction "1_1") (pintype "passive"))
      (node (ref "C51") (pin "1") (pinfunction "1_1") (pintype "passive"))
      (node (ref "C53") (pin "1") (pinfunction "1_1") (pintype "passive"))
      (node (ref "IC15") (pin "1") (pinfunction "VI_1") (pintype "input"))
      (node (ref "IC16") (pin "1") (pinfunction "EN_1") (pintype "passive"))
      (node (ref "IC16") (pin "6") (pinfunction "VBAT_6") (pintype "passive"))
      (node (ref "IC18") (pin "1") (pinfunction "VI_1") (pintype "input"))
      (node (ref "L9") (pin "1") (pinfunction "1_1") (pintype "bidirectional"))
      (node (ref "Q9") (pin "3") (pinfunction "D_3") (pintype "passive"))
      (node (ref "R35") (pin "2") (pinfunction "2_2") (pintype "passive"))
    )
    (net (code "104") (name "Net-(IC16-FB{slash}NC)") (class "Default")
      (node (ref "IC16") (pin "3") (pinfunction "FB/NC_3") (pintype "passive"))
      (node (ref "R29") (pin "1") (pinfunction "1_1") (pintype "passive"))
      (node (ref "R37") (pin "2") (pinfunction "2_2") (pintype "passive"))
    )
    (net (code "105") (name "Net-(IC16-LBI)") (class "Default")
      (node (ref "IC16") (pin "7") (pinfunction "LBI_7") (pintype "passive"))
      (node (ref "R35") (pin "1") (pinfunction "1_1") (pintype "passive"))
      (node (ref "R38") (pin "2") (pinfunction "2_2") (pintype "passive"))
    )
    (net (code "106") (name "Net-(IC16-LX)") (class "Default")
      (node (ref "IC16") (pin "9") (pinfunction "LX_9") (pintype "passive"))
      (node (ref "L9") (pin "2") (pinfunction "2_2") (pintype "bidirectional"))
    )
    (net (code "107") (name "Net-(IC17-DC)") (class "Default")
      (node (ref "IC17") (pin "4") (pinfunction "DC_4") (pintype "input"))
      (node (ref "J15") (pin "1") (pinfunction "1_1") (pintype "passive"))
    )
    (net (code "108") (name "Net-(IC17-~{CHG})") (class "Default")
      (node (ref "IC17") (pin "3") (pinfunction "~{CHG}_3") (pintype "output"))
      (node (ref "LED4") (pin "C") (pinfunction "C_C") (pintype "passive"))
    )
    (net (code "109") (name "Net-(IC18-VO)") (class "Default")
      (node (ref "C54") (pin "1") (pinfunction "1_1") (pintype "passive"))
      (node (ref "IC18") (pin "3") (pinfunction "VO_3") (pintype "passive"))
      (node (ref "J13") (pin "1") (pinfunction "S_1") (pintype "passive"))
      (node (ref "L4") (pin "2") (pinfunction "2_2") (pintype "passive"))
      (node (ref "R20") (pin "2") (pinfunction "2_2") (pintype "passive"))
    )
    (net (code "110") (name "Net-(J6F-S)") (class "Default")
      (node (ref "J6") (pin "6") (pinfunction "S_6") (pintype "passive"))
      (node (ref "Q2") (pin "3") (pinfunction "D_3") (pintype "passive"))
      (node (ref "R13") (pin "1") (pinfunction "1_1") (pintype "passive"))
    )
    (net (code "111") (name "Net-(L5-Pad2)") (class "Default")
      (node (ref "L5") (pin "2") (pinfunction "2_2") (pintype "passive"))
      (node (ref "R20") (pin "1") (pinfunction "1_1") (pintype "passive"))
    )
    (net (code "112") (name "Net-(LED1-PadA)") (class "Default")
      (node (ref "LED1") (pin "A") (pinfunction "A_A") (pintype "passive"))
      (node (ref "R3") (pin "1") (pinfunction "1_1") (pintype "passive"))
    )
    (net (code "113") (name "Net-(LED2-PadC)") (class "Default")
      (node (ref "LED2") (pin "C") (pinfunction "C_C") (pintype "passive"))
      (node (ref "R5") (pin "2") (pinfunction "2_2") (pintype "passive"))
    )
    (net (code "114") (name "Net-(LED3-PadC)") (class "Default")
      (node (ref "LED3") (pin "C") (pinfunction "C_C") (pintype "passive"))
      (node (ref "R6") (pin "2") (pinfunction "2_2") (pintype "passive"))
    )
    (net (code "115") (name "Net-(LED4-PadA)") (class "Default")
      (node (ref "LED4") (pin "A") (pinfunction "A_A") (pintype "passive"))
      (node (ref "R28") (pin "2") (pinfunction "2_2") (pintype "passive"))
    )
    (net (code "116") (name "Net-(LED5-PadA)") (class "Default")
      (node (ref "LED5") (pin "A") (pinfunction "A_A") (pintype "passive"))
      (node (ref "R34") (pin "1") (pinfunction "1_1") (pintype "passive"))
    )
    (net (code "117") (name "Net-(LED6-PadA)") (class "Default")
      (node (ref "LED6") (pin "A") (pinfunction "A_A") (pintype "passive"))
      (node (ref "R32") (pin "1") (pinfunction "1_1") (pintype "passive"))
    )
    (net (code "118") (name "Net-(LED7-PadA)") (class "Default")
      (node (ref "LED7") (pin "A") (pinfunction "A_A") (pintype "passive"))
      (node (ref "R33") (pin "1") (pinfunction "1_1") (pintype "passive"))
    )
    (net (code "119") (name "Net-(Q9-G)") (class "Default")
      (node (ref "J14") (pin "2") (pinfunction "2_2") (pintype "passive"))
      (node (ref "Q9") (pin "1") (pinfunction "G_1") (pintype "passive"))
      (node (ref "R36") (pin "2") (pinfunction "2_2") (pintype "passive"))
    )
    (net (code "120") (name "unconnected-(IC2-CBUS0-Pad12)") (class "Default")
      (node (ref "IC2") (pin "12") (pinfunction "CBUS0_12") (pintype "bidirectional"))
    )
    (net (code "121") (name "unconnected-(IC2-CBUS3-Pad14)") (class "Default")
      (node (ref "IC2") (pin "14") (pinfunction "CBUS3_14") (pintype "bidirectional"))
    )
    (net (code "122") (name "unconnected-(IC2-RTS#-Pad16)") (class "Default")
      (node (ref "IC2") (pin "16") (pinfunction "RTS#_16") (pintype "bidirectional"))
    )
    (net (code "123") (name "unconnected-(IC4-ALERT-Pad3)") (class "Default")
      (node (ref "IC4") (pin "3") (pinfunction "ALERT_3") (pintype "bidirectional"))
    )
    (net (code "124") (name "unconnected-(IC5-NC-Pad5)") (class "Default")
      (node (ref "IC5") (pin "5") (pinfunction "NC_5") (pintype "bidirectional"))
    )
    (net (code "125") (name "unconnected-(IC6-(A8)PC0-Pad35)") (class "Default")
      (node (ref "IC6") (pin "35") (pinfunction "(A8)PC0_35") (pintype "bidirectional"))
    )
    (net (code "126") (name "unconnected-(IC6-(A9)PC1-Pad36)") (class "Default")
      (node (ref "IC6") (pin "36") (pinfunction "(A9)PC1_36") (pintype "bidirectional"))
    )
    (net (code "127") (name "unconnected-(IC6-(A10)PC2-Pad37)") (class "Default")
      (node (ref "IC6") (pin "37") (pinfunction "(A10)PC2_37") (pintype "bidirectional"))
    )
    (net (code "128") (name "unconnected-(IC6-(A11)PC3-Pad38)") (class "Default")
      (node (ref "IC6") (pin "38") (pinfunction "(A11)PC3_38") (pintype "bidirectional"))
    )
    (net (code "129") (name "unconnected-(IC6-(A12)PC4-Pad39)") (class "Default")
      (node (ref "IC6") (pin "39") (pinfunction "(A12)PC4_39") (pintype "bidirectional"))
    )
    (net (code "130") (name "unconnected-(IC6-(A13)PC5-Pad40)") (class "Default")
      (node (ref "IC6") (pin "40") (pinfunction "(A13)PC5_40") (pintype "bidirectional"))
    )
    (net (code "131") (name "unconnected-(IC6-(A14)PC6-Pad41)") (class "Default")
      (node (ref "IC6") (pin "41") (pinfunction "(A14)PC6_41") (pintype "bidirectional"))
    )
    (net (code "132") (name "unconnected-(IC6-(A15)PC7-Pad42)") (class "Default")
      (node (ref "IC6") (pin "42") (pinfunction "(A15)PC7_42") (pintype "bidirectional"))
    )
    (net (code "133") (name "unconnected-(IC6-(AD0)PA0-Pad51)") (class "Default")
      (node (ref "IC6") (pin "51") (pinfunction "(AD0)PA0_51") (pintype "bidirectional"))
    )
    (net (code "134") (name "unconnected-(IC6-(AD1)PA1-Pad50)") (class "Default")
      (node (ref "IC6") (pin "50") (pinfunction "(AD1)PA1_50") (pintype "bidirectional"))
    )
    (net (code "135") (name "unconnected-(IC6-(AD2)PA2-Pad49)") (class "Default")
      (node (ref "IC6") (pin "49") (pinfunction "(AD2)PA2_49") (pintype "bidirectional"))
    )
    (net (code "136") (name "unconnected-(IC6-(AD3)PA3-Pad48)") (class "Default")
      (node (ref "IC6") (pin "48") (pinfunction "(AD3)PA3_48") (pintype "bidirectional"))
    )
    (net (code "137") (name "unconnected-(IC6-(AD4)PA4-Pad47)") (class "Default")
      (node (ref "IC6") (pin "47") (pinfunction "(AD4)PA4_47") (pintype "bidirectional"))
    )
    (net (code "138") (name "unconnected-(IC6-(AD5)PA5-Pad46)") (class "Default")
      (node (ref "IC6") (pin "46") (pinfunction "(AD5)PA5_46") (pintype "bidirectional"))
    )
    (net (code "139") (name "unconnected-(IC6-(AD6)PA6-Pad45)") (class "Default")
      (node (ref "IC6") (pin "45") (pinfunction "(AD6)PA6_45") (pintype "bidirectional"))
    )
    (net (code "140") (name "unconnected-(IC6-(AD7)PA7-Pad44)") (class "Default")
      (node (ref "IC6") (pin "44") (pinfunction "(AD7)PA7_44") (pintype "bidirectional"))
    )
    (net (code "141") (name "unconnected-(IC6-(ADC0)PF0-Pad61)") (class "Default")
      (node (ref "IC6") (pin "61") (pinfunction "(ADC0)PF0_61") (pintype "bidirectional"))
    )
    (net (code "142") (name "unconnected-(IC6-(ADC1)PF1-Pad60)") (class "Default")
      (node (ref "IC6") (pin "60") (pinfunction "(ADC1)PF1_60") (pintype "bidirectional"))
    )
    (net (code "143") (name "unconnected-(IC6-(ADC2)PF2-Pad59)") (class "Default")
      (node (ref "IC6") (pin "59") (pinfunction "(ADC2)PF2_59") (pintype "bidirectional"))
    )
    (net (code "144") (name "unconnected-(IC6-(ADC3)PF3-Pad58)") (class "Default")
      (node (ref "IC6") (pin "58") (pinfunction "(ADC3)PF3_58") (pintype "bidirectional"))
    )
    (net (code "145") (name "unconnected-(IC6-(ADC4{slash}TCK)PF4-Pad57)") (class "Default")
      (node (ref "IC6") (pin "57") (pinfunction "(ADC4/TCK)PF4_57") (pintype "bidirectional"))
    )
    (net (code "146") (name "unconnected-(IC6-(ADC5{slash}TMS)PF5-Pad56)") (class "Default")
      (node (ref "IC6") (pin "56") (pinfunction "(ADC5/TMS)PF5_56") (pintype "bidirectional"))
    )
    (net (code "147") (name "unconnected-(IC6-(ADC6{slash}TDO)PF6-Pad55)") (class "Default")
      (node (ref "IC6") (pin "55") (pinfunction "(ADC6/TDO)PF6_55") (pintype "bidirectional"))
    )
    (net (code "148") (name "unconnected-(IC6-(ADC7{slash}TDI)PF7-Pad54)") (class "Default")
      (node (ref "IC6") (pin "54") (pinfunction "(ADC7/TDI)PF7_54") (pintype "bidirectional"))
    )
    (net (code "149") (name "unconnected-(IC6-(ALE)PG2-Pad43)") (class "Default")
      (node (ref "IC6") (pin "43") (pinfunction "(ALE)PG2_43") (pintype "bidirectional"))
    )
    (net (code "150") (name "unconnected-(IC6-(OC0A{slash}OC1C{slash}PCINT7)PB7-Pad17)") (class "Default")
      (node (ref "IC6") (pin "17") (pinfunction "(OC0A/OC1C/PCINT7)PB7_17") (pintype "bidirectional"))
    )
    (net (code "151") (name "unconnected-(IC6-(OC0B)PG5-Pad1)") (class "Default")
      (node (ref "IC6") (pin "1") (pinfunction "(OC0B)PG5_1") (pintype "bidirectional"))
    )
    (net (code "152") (name "unconnected-(IC6-(OC1A{slash}PCINT5)PB5-Pad15)") (class "Default")
      (node (ref "IC6") (pin "15") (pinfunction "(OC1A/PCINT5)PB5_15") (pintype "bidirectional"))
    )
    (net (code "153") (name "unconnected-(IC6-(OC1B{slash}PCINT6)PB6-Pad16)") (class "Default")
      (node (ref "IC6") (pin "16") (pinfunction "(OC1B/PCINT6)PB6_16") (pintype "bidirectional"))
    )
    (net (code "154") (name "unconnected-(IC6-(OC2A{slash}PCINT4)PB4-Pad14)") (class "Default")
      (node (ref "IC6") (pin "14") (pinfunction "(OC2A/PCINT4)PB4_14") (pintype "bidirectional"))
    )
    (net (code "155") (name "unconnected-(IC6-(RD)PG1-Pad34)") (class "Default")
      (node (ref "IC6") (pin "34") (pinfunction "(RD)PG1_34") (pintype "bidirectional"))
    )
    (net (code "156") (name "unconnected-(IC6-(SS{slash}PCINT0)PB0-Pad10)") (class "Default")
      (node (ref "IC6") (pin "10") (pinfunction "(SS/PCINT0)PB0_10") (pintype "bidirectional"))
    )
    (net (code "157") (name "unconnected-(IC6-(T0)PD7-Pad32)") (class "Default")
      (node (ref "IC6") (pin "32") (pinfunction "(T0)PD7_32") (pintype "bidirectional"))
    )
    (net (code "158") (name "unconnected-(IC6-(T1)PD6-Pad31)") (class "Default")
      (node (ref "IC6") (pin "31") (pinfunction "(T1)PD6_31") (pintype "bidirectional"))
    )
    (net (code "159") (name "unconnected-(IC6-(TOSC1)PG4-Pad19)") (class "Default")
      (node (ref "IC6") (pin "19") (pinfunction "(TOSC1)PG4_19") (pintype "bidirectional"))
    )
    (net (code "160") (name "unconnected-(IC6-(TOSC2)PG3-Pad18)") (class "Default")
      (node (ref "IC6") (pin "18") (pinfunction "(TOSC2)PG3_18") (pintype "bidirectional"))
    )
    (net (code "161") (name "unconnected-(IC6-(WR)PG0-Pad33)") (class "Default")
      (node (ref "IC6") (pin "33") (pinfunction "(WR)PG0_33") (pintype "bidirectional"))
    )
    (net (code "162") (name "unconnected-(IC6-(XCK1)PD5-Pad30)") (class "Default")
      (node (ref "IC6") (pin "30") (pinfunction "(XCK1)PD5_30") (pintype "bidirectional"))
    )
    (net (code "163") (name "unconnected-(IC9-NC-Pad8)") (class "Default")
      (node (ref "IC9") (pin "8") (pinfunction "NC_8") (pintype "bidirectional"))
    )
    (net (code "164") (name "unconnected-(IC9-NC-Pad9)") (class "Default")
      (node (ref "IC9") (pin "9") (pinfunction "NC_9") (pintype "bidirectional"))
    )
    (net (code "165") (name "unconnected-(IC9-RES-Pad5)") (class "Default")
      (node (ref "IC9") (pin "5") (pinfunction "RES_5") (pintype "bidirectional"))
    )
    (net (code "166") (name "unconnected-(IC9-RES-Pad10)") (class "Default")
      (node (ref "IC9") (pin "10") (pinfunction "RES_10") (pintype "bidirectional"))
    )
    (net (code "167") (name "unconnected-(IC9-RES-Pad11)") (class "Default")
      (node (ref "IC9") (pin "11") (pinfunction "RES_11") (pintype "bidirectional"))
    )
    (net (code "168") (name "unconnected-(IC9-RES-Pad13)") (class "Default")
      (node (ref "IC9") (pin "13") (pinfunction "RES_13") (pintype "bidirectional"))
    )
    (net (code "169") (name "unconnected-(IC9-RES-Pad14)") (class "Default")
      (node (ref "IC9") (pin "14") (pinfunction "RES_14") (pintype "bidirectional"))
    )
    (net (code "170") (name "unconnected-(IC9-VDD_M-Pad21)") (class "Default")
      (node (ref "IC9") (pin "21") (pinfunction "VDD_M_21") (pintype "bidirectional"))
    )
    (net (code "171") (name "unconnected-(IC10-NC-Pad1)") (class "Default")
      (node (ref "IC10") (pin "1") (pinfunction "NC_1") (pintype "no_connect"))
    )
    (net (code "172") (name "unconnected-(IC10-NC-Pad5)") (class "Default")
      (node (ref "IC10") (pin "5") (pinfunction "NC_5") (pintype "no_connect"))
    )
    (net (code "173") (name "unconnected-(IC10-NC-Pad6)") (class "Default")
      (node (ref "IC10") (pin "6") (pinfunction "NC_6") (pintype "no_connect"))
    )
    (net (code "174") (name "unconnected-(IC13-NC1-Pad14)") (class "Default")
      (node (ref "IC13") (pin "14") (pinfunction "NC1_14") (pintype "no_connect"))
    )
    (net (code "175") (name "unconnected-(IC13-NC2-Pad21)") (class "Default")
      (node (ref "IC13") (pin "21") (pinfunction "NC2_21") (pintype "no_connect"))
    )
    (net (code "176") (name "unconnected-(IC13-NC3-Pad22)") (class "Default")
      (node (ref "IC13") (pin "22") (pinfunction "NC3_22") (pintype "no_connect"))
    )
    (net (code "177") (name "unconnected-(IC13-P0.1{slash}AGND-Pad35)") (class "Default")
      (node (ref "IC13") (pin "35") (pinfunction "P0.1/AGND_35") (pintype "bidirectional"))
    )
    (net (code "178") (name "unconnected-(IC13-P0.2{slash}XTAL1-Pad34)") (class "Default")
      (node (ref "IC13") (pin "34") (pinfunction "P0.2/XTAL1_34") (pintype "bidirectional"))
    )
    (net (code "179") (name "unconnected-(IC13-P0.3{slash}XTAL2-Pad33)") (class "Default")
      (node (ref "IC13") (pin "33") (pinfunction "P0.3/XTAL2_33") (pintype "bidirectional"))
    )
    (net (code "180") (name "unconnected-(IC13-P2.6-Pad41)") (class "Default")
      (node (ref "IC13") (pin "41") (pinfunction "P2.6_41") (pintype "bidirectional"))
    )
    (net (code "181") (name "unconnected-(J1-CARD_DETECT1-PadCD2)") (class "Default")
      (node (ref "J1") (pin "CD2") (pinfunction "CARD_DETECT1_CD2") (pintype "passive"))
    )
    (net (code "182") (name "unconnected-(J1-DAT1-Pad8)") (class "Default")
      (node (ref "J1") (pin "8") (pinfunction "DAT1_8") (pintype "bidirectional"))
    )
    (net (code "183") (name "unconnected-(J1-DAT2-Pad1)") (class "Default")
      (node (ref "J1") (pin "1") (pinfunction "DAT2_1") (pintype "bidirectional"))
    )
    (net (code "184") (name "unconnected-(X1-PadGND)") (class "Default")
      (node (ref "X1") (pin "GND") (pinfunction "GND_GND") (pintype "bidirectional"))
    )
  )
)
